# Linux_board_va_1_dxp.net
KiCad netlist of a schematic drawn in Altium Designer
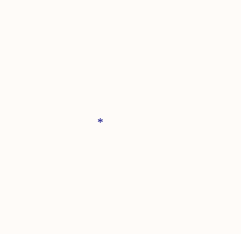
[diagram p0: Linux_board.va_1.dxp.SchDoc, top left]
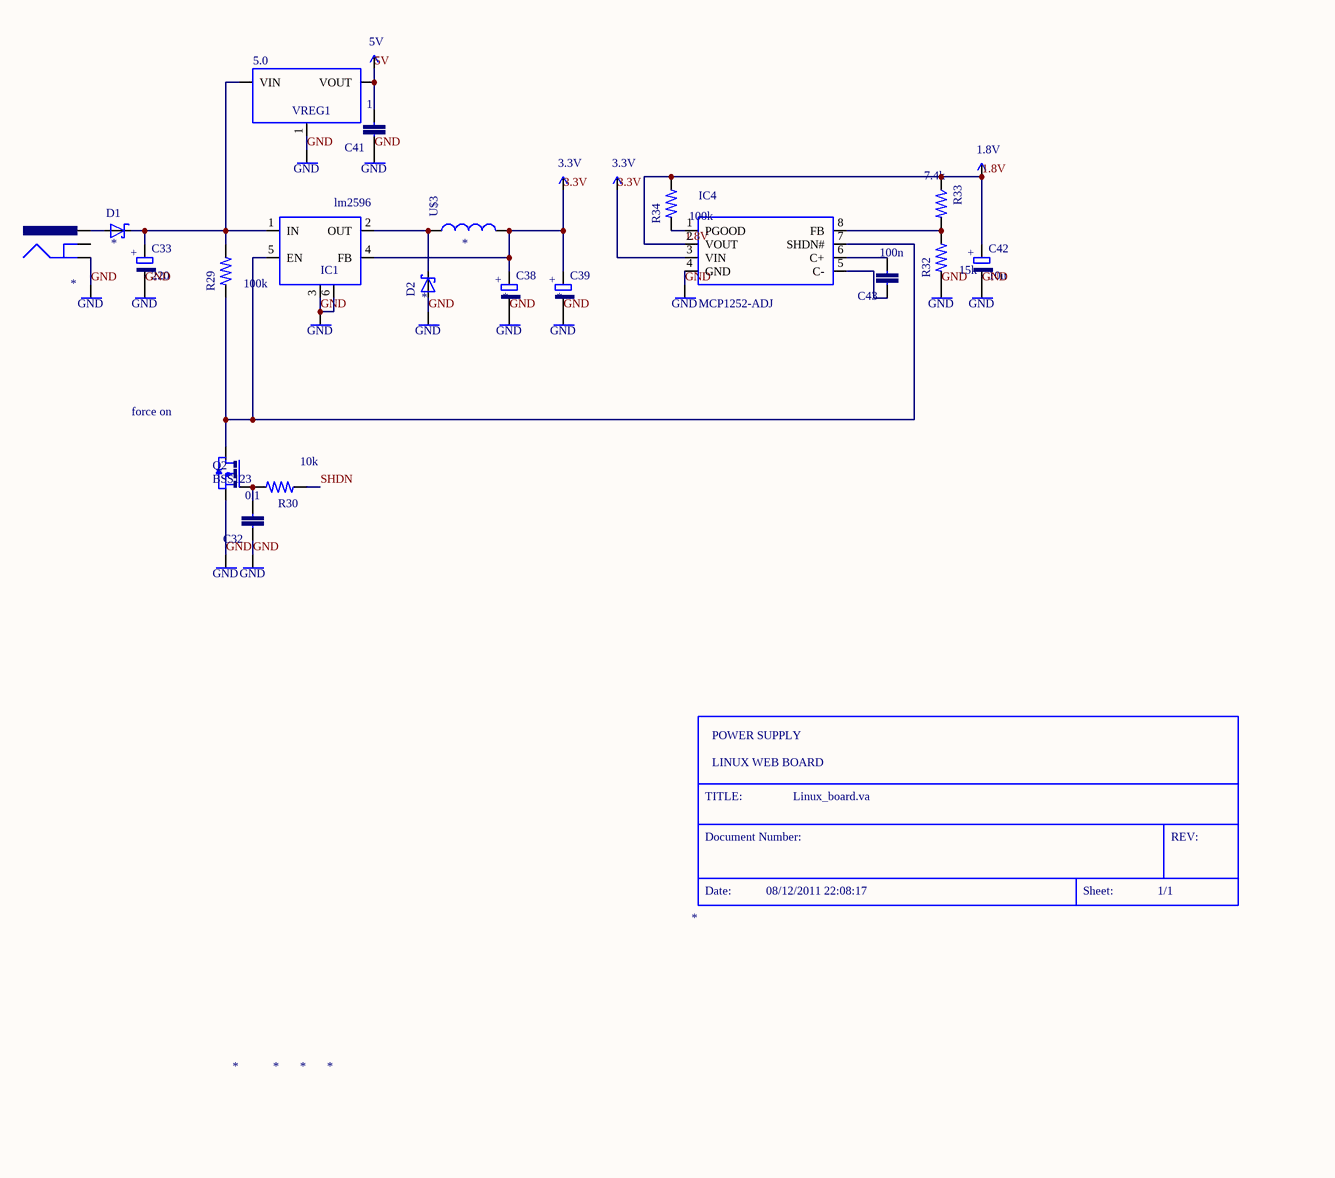
[diagram p1: Linux_board.va_1.dxp.SchDoc, top middle]
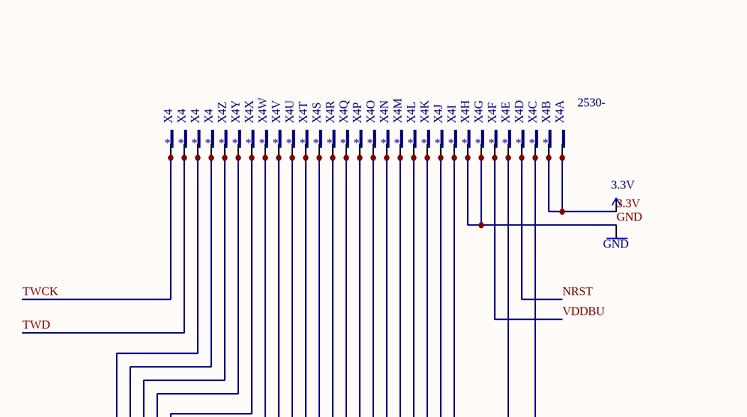
[diagram p2: Linux_board.va_1.dxp.SchDoc, top right]
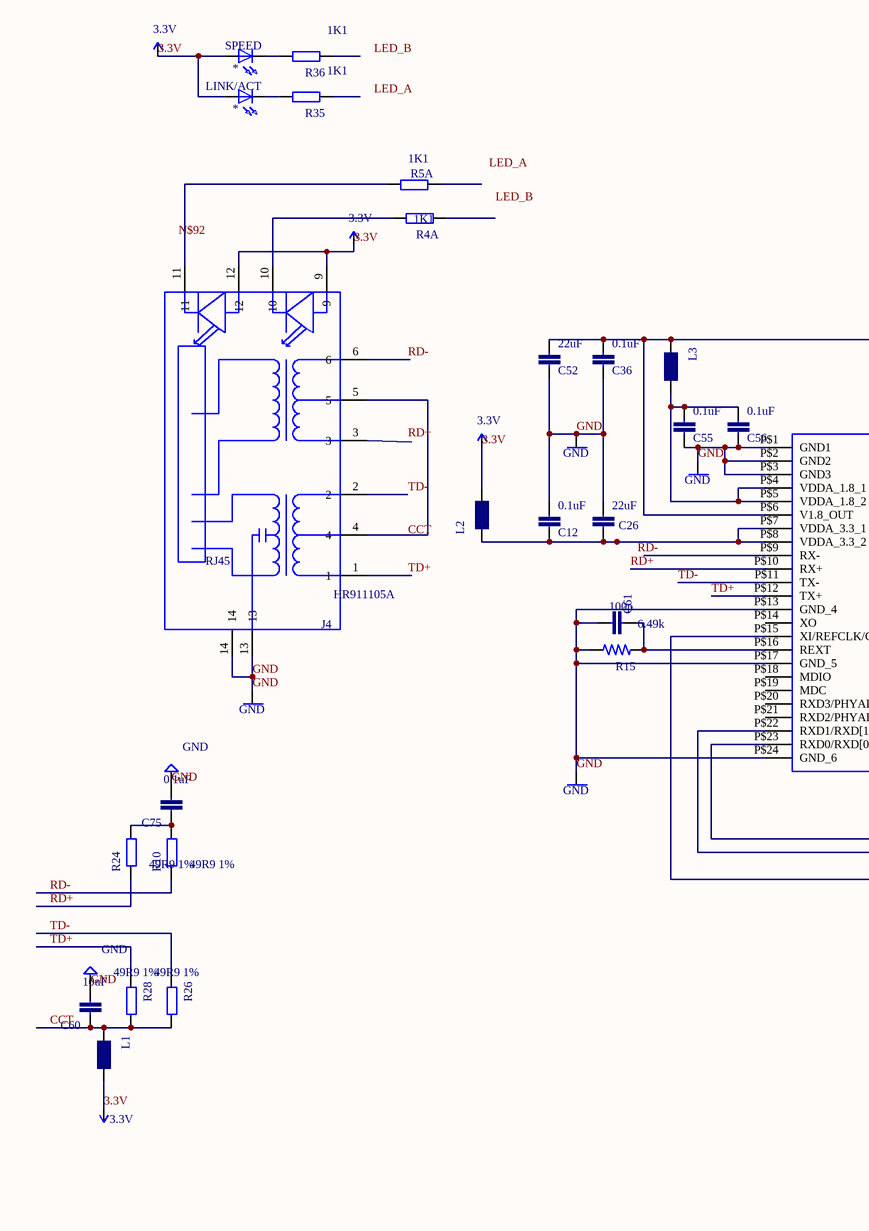
[diagram p3: Linux_board.va_1.dxp.SchDoc, bottom left]
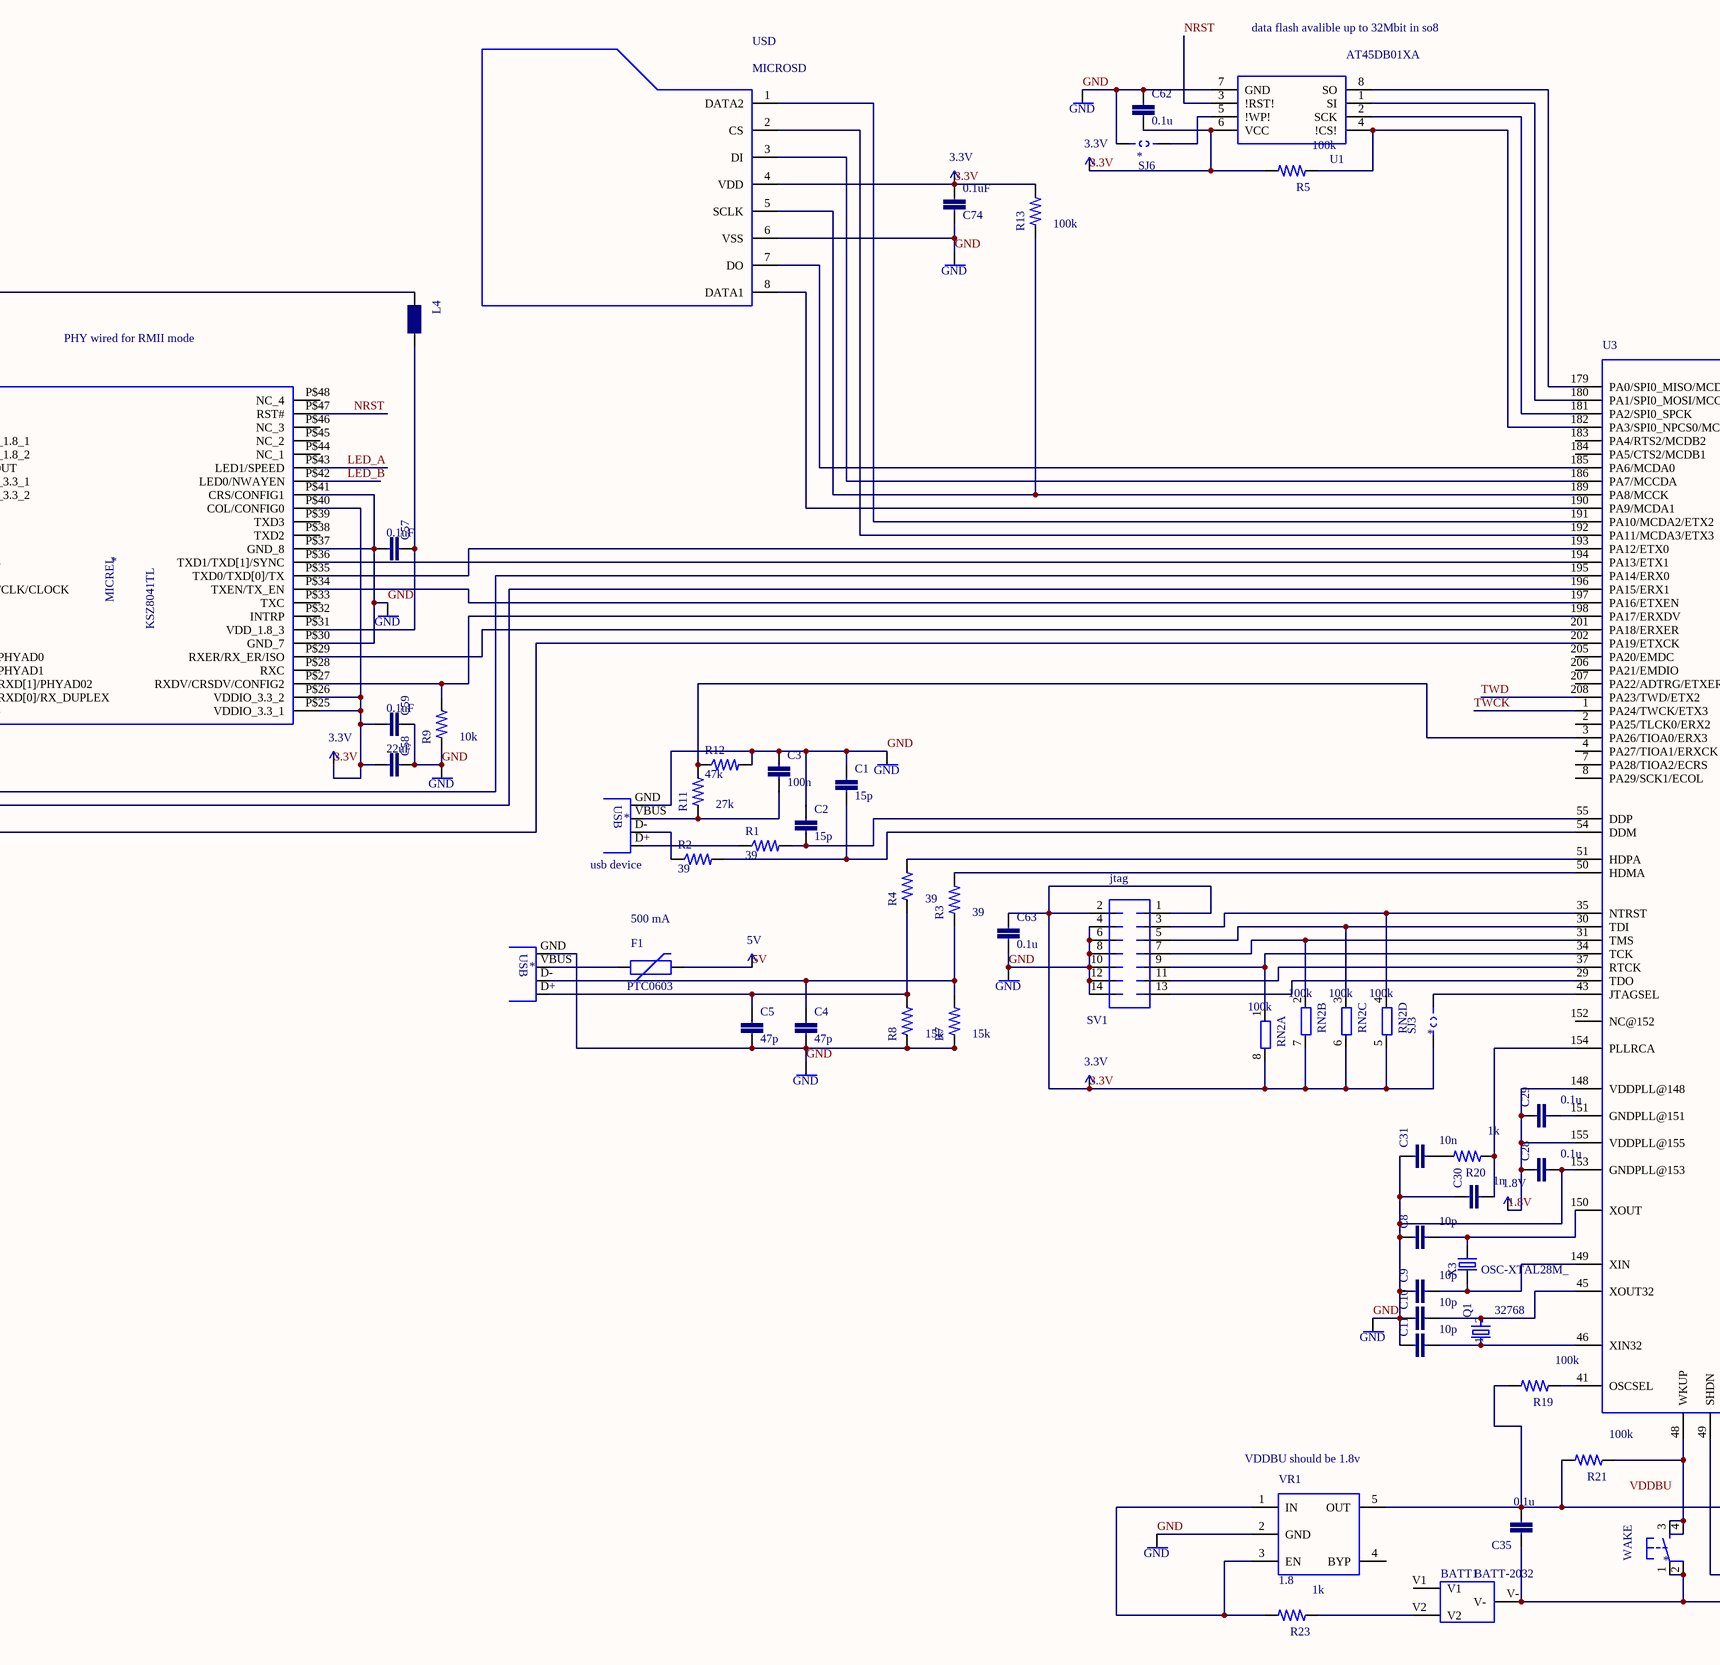
[diagram p4: Linux_board.va_1.dxp.SchDoc, bottom middle]
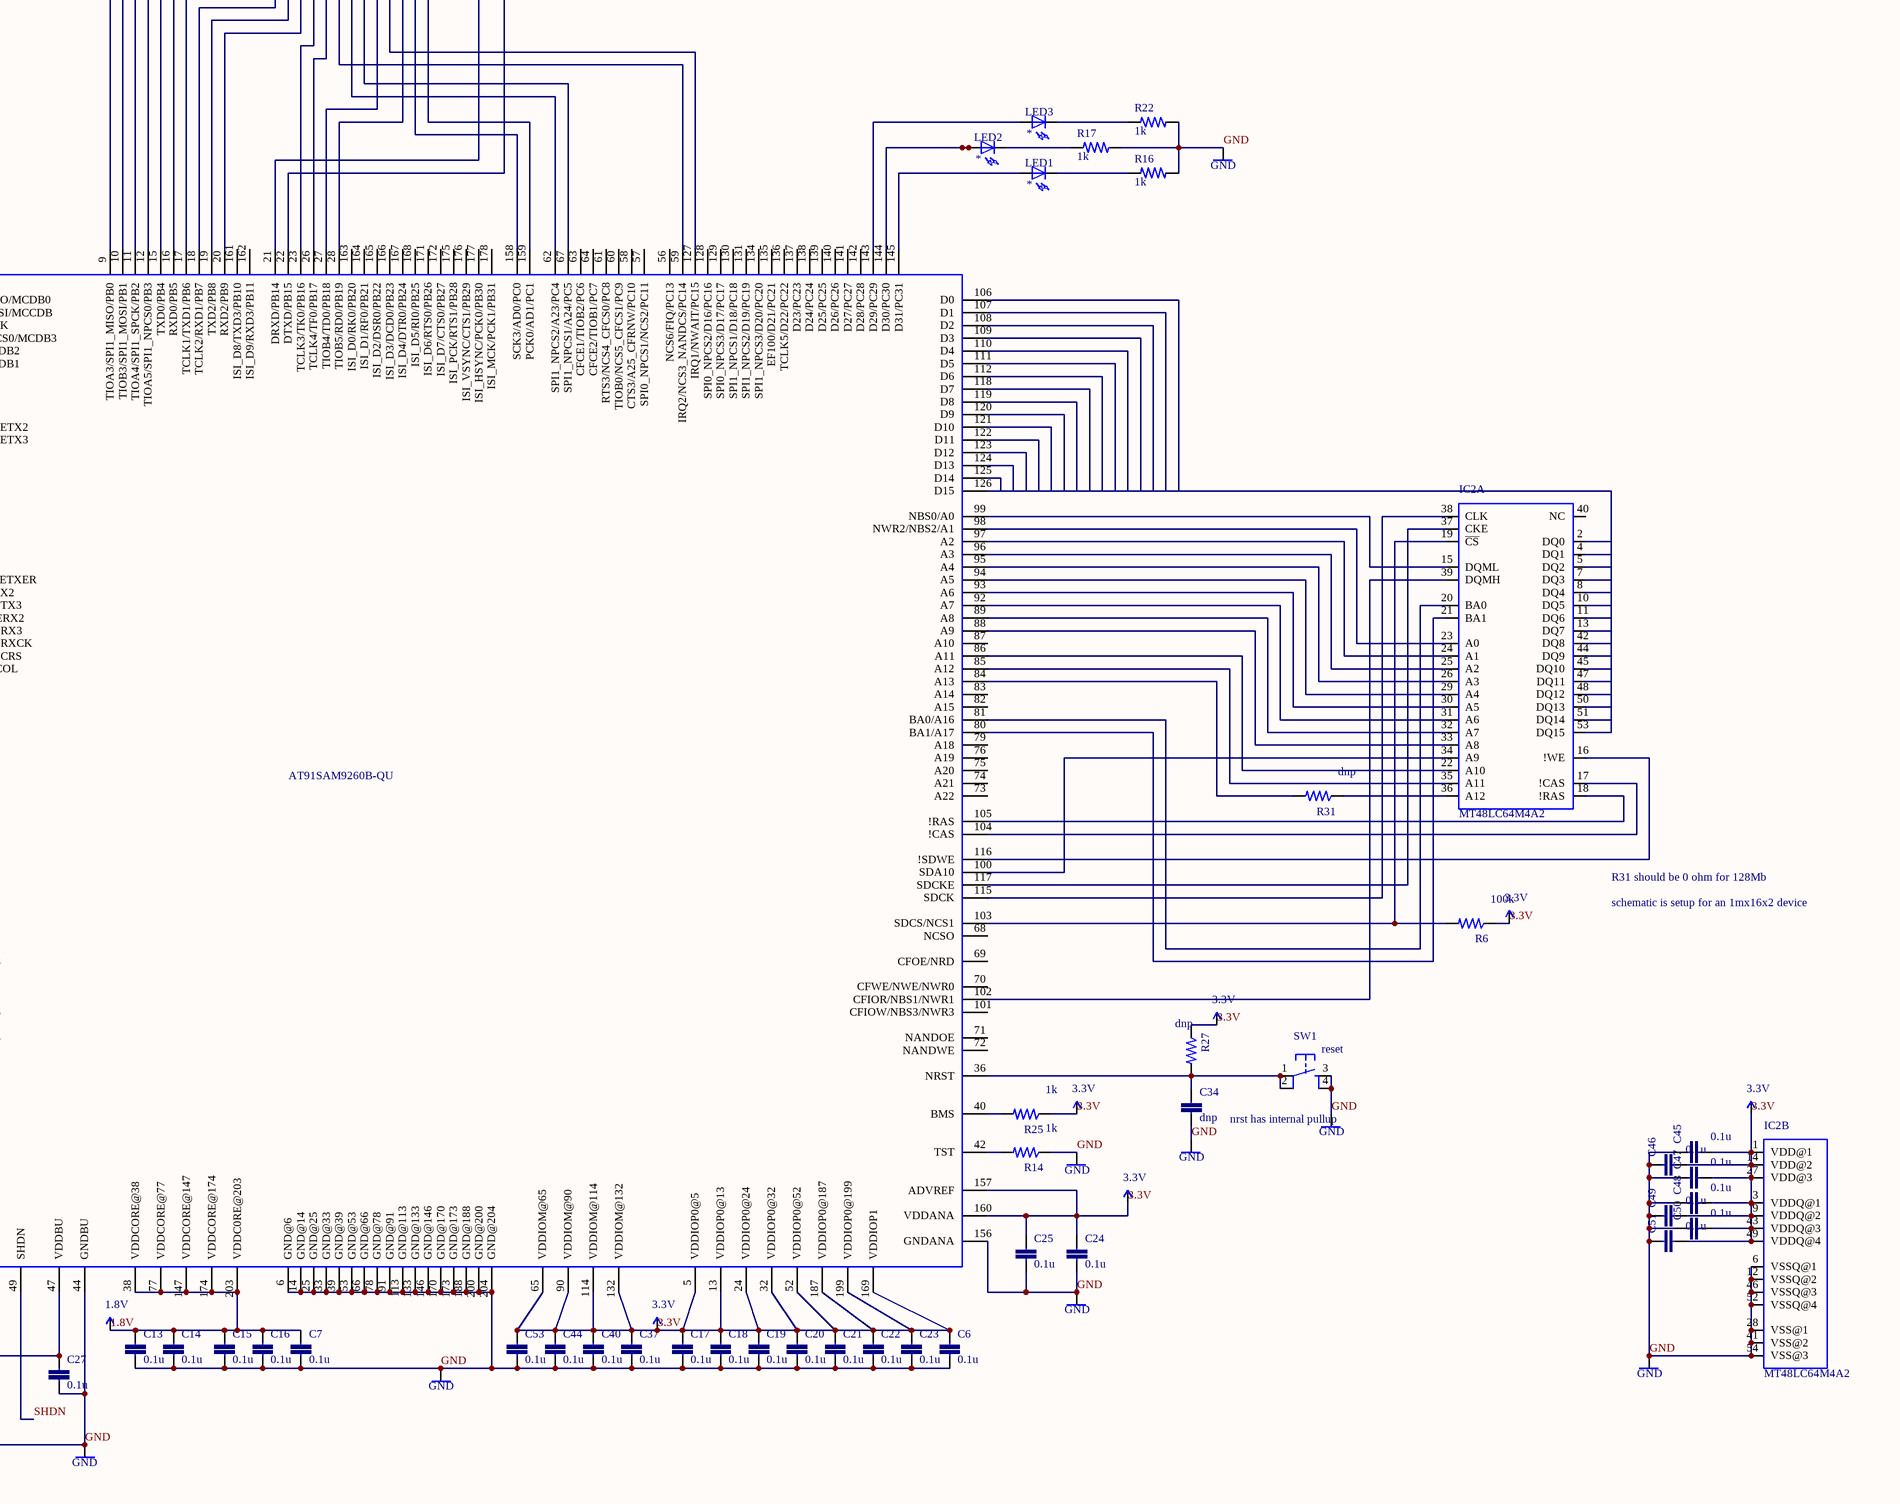
[diagram p5: Linux_board.va_1.dxp.SchDoc, bottom right]

(export (version "E")
  (design (tool "Eeschema 10.0.6"))
  (components
    (comp (ref "BATT1")
      (value "BATT-2032")
      (footprint "2032")
      (libsource (lib "dp_devices") (part "BATT-2032"))
    )
    (comp (ref "C1") (value "15p") (footprint "0603-CAP") (libsource (lib "SparkFun") (part "CAP0603-CAP")))
    (comp (ref "C2") (value "15p") (footprint "0603-CAP") (libsource (lib "SparkFun") (part "CAP0603-CAP")))
    (comp (ref "C3") (value "100n") (footprint "0603-CAP") (libsource (lib "SparkFun") (part "CAP0603-CAP")))
    (comp (ref "C4") (value "47p") (footprint "0603-CAP") (libsource (lib "SparkFun") (part "CAP0603-CAP")))
    (comp (ref "C5") (value "47p") (footprint "0603-CAP") (libsource (lib "SparkFun") (part "CAP0603-CAP")))
    (comp (ref "C6") (value "0.1u") (footprint "0603-CAP") (libsource (lib "SparkFun") (part "CAP0603-CAP")))
    (comp (ref "C7") (value "0.1u") (footprint "0603-CAP") (libsource (lib "SparkFun") (part "CAP0603-CAP")))
    (comp (ref "C8") (value "10p") (footprint "0603-CAP") (libsource (lib "") (part "CAP0603-CAP_1")))
    (comp (ref "C9") (value "10p") (footprint "0603-CAP") (libsource (lib "") (part "CAP0603-CAP_1")))
    (comp (ref "C10") (value "10p") (footprint "0603-CAP") (libsource (lib "") (part "CAP0603-CAP_1")))
    (comp (ref "C11") (value "10p") (footprint "0603-CAP") (libsource (lib "") (part "CAP0603-CAP_1")))
    (comp (ref "C12") (value "0.1uF") (footprint "C0603") (libsource (lib "") (part "C-EUC0603_1")))
    (comp (ref "C13") (value "0.1u") (footprint "0603-CAP") (libsource (lib "SparkFun") (part "CAP0603-CAP")))
    (comp (ref "C14") (value "0.1u") (footprint "0603-CAP") (libsource (lib "SparkFun") (part "CAP0603-CAP")))
    (comp (ref "C15") (value "0.1u") (footprint "0603-CAP") (libsource (lib "SparkFun") (part "CAP0603-CAP")))
    (comp (ref "C16") (value "0.1u") (footprint "0603-CAP") (libsource (lib "SparkFun") (part "CAP0603-CAP")))
    (comp (ref "C17") (value "0.1u") (footprint "0603-CAP") (libsource (lib "SparkFun") (part "CAP0603-CAP")))
    (comp (ref "C18") (value "0.1u") (footprint "0603-CAP") (libsource (lib "SparkFun") (part "CAP0603-CAP")))
    (comp (ref "C19") (value "0.1u") (footprint "0603-CAP") (libsource (lib "SparkFun") (part "CAP0603-CAP")))
    (comp (ref "C20") (value "0.1u") (footprint "0603-CAP") (libsource (lib "SparkFun") (part "CAP0603-CAP")))
    (comp (ref "C21") (value "0.1u") (footprint "0603-CAP") (libsource (lib "SparkFun") (part "CAP0603-CAP")))
    (comp (ref "C22") (value "0.1u") (footprint "0603-CAP") (libsource (lib "SparkFun") (part "CAP0603-CAP")))
    (comp (ref "C23") (value "0.1u") (footprint "0603-CAP") (libsource (lib "SparkFun") (part "CAP0603-CAP")))
    (comp (ref "C24") (value "0.1u") (footprint "0603-CAP") (libsource (lib "SparkFun") (part "CAP0603-CAP")))
    (comp (ref "C25") (value "0.1u") (footprint "0603-CAP") (libsource (lib "SparkFun") (part "CAP0603-CAP")))
    (comp (ref "C26") (value "22uF") (footprint "C0603") (libsource (lib "") (part "C-EUC0603_1")))
    (comp (ref "C27") (value "0.1u") (footprint "0603-CAP") (libsource (lib "SparkFun") (part "CAP0603-CAP")))
    (comp (ref "C28") (value "0.1u") (footprint "0603-CAP") (libsource (lib "") (part "CAP0603-CAP_1")))
    (comp (ref "C29") (value "0.1u") (footprint "0603-CAP") (libsource (lib "") (part "CAP0603-CAP_1")))
    (comp (ref "C30") (value "1n") (footprint "0603-CAP") (libsource (lib "") (part "CAP0603-CAP_1")))
    (comp (ref "C31") (value "10n") (footprint "0603-CAP") (libsource (lib "") (part "CAP0603-CAP_1")))
    (comp (ref "C32") (value "0.1") (footprint "C603") (libsource (lib "dp_devices") (part "CAPC603")))
    (comp (ref "C33") (value "220") (footprint "SMC_B") (libsource (lib "dp_devices") (part "CAP_POLSMC_B")))
    (comp (ref "C34") (value "dnp") (footprint "0603-CAP") (libsource (lib "SparkFun") (part "CAP0603-CAP")))
    (comp (ref "C35") (value "0.1u") (footprint "0603-CAP") (libsource (lib "") (part "CAP0603-CAP_2")))
    (comp (ref "C36") (value "0.1uF") (footprint "C0603") (libsource (lib "") (part "C-EUC0603_1")))
    (comp (ref "C37") (value "0.1u") (footprint "0603-CAP") (libsource (lib "SparkFun") (part "CAP0603-CAP")))
    (comp (ref "C38") (value "*") (footprint "CASE_A") (libsource (lib "dp_devices") (part "CAP_POLCASE_A")))
    (comp (ref "C39") (value "*") (footprint "SMC_B") (libsource (lib "dp_devices") (part "CAP_POLSMC_B")))
    (comp (ref "C40") (value "0.1u") (footprint "0603-CAP") (libsource (lib "SparkFun") (part "CAP0603-CAP")))
    (comp (ref "C41") (value "1") (footprint "C603") (libsource (lib "dp_devices") (part "CAPC603")))
    (comp (ref "C42") (value "10u") (footprint "SMC_B") (libsource (lib "dp_devices") (part "CAP_POLSMC_B")))
    (comp (ref "C43") (value "100n") (footprint "C603") (libsource (lib "dp_devices") (part "CAPC603")))
    (comp (ref "C44") (value "0.1u") (footprint "0603-CAP") (libsource (lib "SparkFun") (part "CAP0603-CAP")))
    (comp (ref "C45") (value "0.1u") (footprint "0603-CAP") (libsource (lib "") (part "CAP0603-CAP_1")))
    (comp (ref "C46") (value "0.1u") (footprint "0603-CAP") (libsource (lib "") (part "CAP0603-CAP_1")))
    (comp (ref "C47") (value "0.1u") (footprint "0603-CAP") (libsource (lib "") (part "CAP0603-CAP_1")))
    (comp (ref "C48") (value "0.1u") (footprint "0603-CAP") (libsource (lib "") (part "CAP0603-CAP_1")))
    (comp (ref "C49") (value "0.1u") (footprint "0603-CAP") (libsource (lib "") (part "CAP0603-CAP_1")))
    (comp (ref "C50") (value "0.1u") (footprint "0603-CAP") (libsource (lib "") (part "CAP0603-CAP_1")))
    (comp (ref "C51") (value "0.1u") (footprint "0603-CAP") (libsource (lib "") (part "CAP0603-CAP_1")))
    (comp (ref "C52") (value "22uF") (footprint "C0603") (libsource (lib "") (part "C-EUC0603_1")))
    (comp (ref "C53") (value "0.1u") (footprint "0603-CAP") (libsource (lib "SparkFun") (part "CAP0603-CAP")))
    (comp (ref "C55") (value "0.1uF") (footprint "C0603") (libsource (lib "") (part "C-EUC0603_1")))
    (comp (ref "C56") (value "0.1uF") (footprint "C0603") (libsource (lib "") (part "C-EUC0603_1")))
    (comp (ref "C57") (value "0.1uF") (footprint "C0603") (libsource (lib "rcl") (part "C-EUC0603")))
    (comp (ref "C58") (value "22uF") (footprint "C0603") (libsource (lib "rcl") (part "C-EUC0603")))
    (comp (ref "C59") (value "0.1uF") (footprint "C0603") (libsource (lib "rcl") (part "C-EUC0603")))
    (comp (ref "C60") (value "10uF") (footprint "C0603") (libsource (lib "") (part "C-EUC0603_2")))
    (comp (ref "C61") (value "100p") (footprint "C0603") (libsource (lib "rcl") (part "C-EUC0603")))
    (comp (ref "C62") (value "0.1u") (footprint "0603-CAP") (libsource (lib "SparkFun") (part "CAP0603-CAP")))
    (comp (ref "C63") (value "0.1u") (footprint "0603-CAP") (libsource (lib "SparkFun") (part "CAP0603-CAP")))
    (comp (ref "C74") (value "0.1uF") (footprint "C0603") (libsource (lib "") (part "C-EUC0603_1")))
    (comp (ref "C75") (value "0.1uF") (footprint "C0603") (libsource (lib "") (part "C-EUC0603_2")))
    (comp (ref "D1") (value "*") (footprint "SMB") (libsource (lib "diode") (part "SCHOTTKY-DIODESMD")))
    (comp (ref "D2") (value "*") (footprint "SMB") (libsource (lib "") (part "SCHOTTKY-DIODESMD_1")))
    (comp (ref "F1") (value "PTC0603") (footprint "0603") (libsource (lib "SparkFun") (part "PTC0603")))
    (comp (ref "FRAME1") (value "*") (libsource (lib "") (part "FRAME_A_L_1")))
    (comp (ref "GND1") (value "GND") (libsource (lib "") (part "GND_1")))
    (comp (ref "GND2") (value "GND") (libsource (lib "") (part "GND_1")))
    (comp (ref "GND3") (value "GND") (libsource (lib "") (part "GND_1")))
    (comp (ref "GND4") (value "GND") (libsource (lib "") (part "GND_1")))
    (comp (ref "GND6") (value "GND") (libsource (lib "") (part "GND_1")))
    (comp (ref "GND7") (value "GND") (libsource (lib "") (part "GND_1")))
    (comp (ref "GND8") (value "GND") (libsource (lib "") (part "GND_1")))
    (comp (ref "GND9") (value "GND") (libsource (lib "") (part "GND_1")))
    (comp (ref "GND10") (value "GND") (libsource (lib "supply1") (part "GND")))
    (comp (ref "GND11") (value "GND") (libsource (lib "supply1") (part "GND")))
    (comp (ref "GND12") (value "GND") (libsource (lib "") (part "GND_1")))
    (comp (ref "GND13") (value "GND") (libsource (lib "supply1") (part "GND")))
    (comp (ref "GND14") (value "GND") (libsource (lib "") (part "GND_1")))
    (comp (ref "GND15") (value "GND") (libsource (lib "supply1") (part "GND")))
    (comp (ref "GND16") (value "GND") (libsource (lib "") (part "GND_1")))
    (comp (ref "GND17") (value "GND") (libsource (lib "") (part "GND_1")))
    (comp (ref "GND18") (value "GND") (libsource (lib "") (part "GND_1")))
    (comp (ref "GND19") (value "GND") (libsource (lib "") (part "GND_1")))
    (comp (ref "GND20") (value "GND") (libsource (lib "") (part "GND_1")))
    (comp (ref "GND21") (value "GND") (libsource (lib "") (part "GND_1")))
    (comp (ref "GND22") (value "GND") (libsource (lib "") (part "GND_1")))
    (comp (ref "GND23") (value "GND") (libsource (lib "supply1") (part "GND")))
    (comp (ref "GND24") (value "GND") (libsource (lib "supply1") (part "GND")))
    (comp (ref "GND25") (value "GND") (libsource (lib "") (part "GND_1")))
    (comp (ref "GND26") (value "GND") (libsource (lib "") (part "GND_1")))
    (comp (ref "GND27") (value "GND") (libsource (lib "") (part "GND_1")))
    (comp (ref "GND28") (value "GND") (libsource (lib "") (part "GND_1")))
    (comp (ref "GND29") (value "GND") (libsource (lib "") (part "GND_1")))
    (comp (ref "GND30") (value "GND") (libsource (lib "") (part "GND_1")))
    (comp (ref "GND31") (value "GND") (libsource (lib "") (part "GND_1")))
    (comp (ref "GND32") (value "GND") (libsource (lib "") (part "GND_1")))
    (comp (ref "GND33") (value "GND") (libsource (lib "") (part "GND_1")))
    (comp (ref "GND34") (value "GND") (libsource (lib "") (part "GND_1")))
    (comp (ref "GND35") (value "GND") (libsource (lib "") (part "GND_1")))
    (comp (ref "GND36") (value "GND") (libsource (lib "") (part "GND_1")))
    (comp (ref "IC1") (value "lm2596") (footprint "TO263-5") (libsource (lib "linear") (part "LM2596S")))
    (comp (ref "IC2")
      (value "MT48LC64M4A2")
      (footprint "TSOP54-400")
      (libsource (lib "") (part "MT48LC64M4A2_1"))
    )
    (comp (ref "IC4")
      (value "MCP1252-ADJ")
      (footprint "MSOP8")
      (libsource (lib "microchip-dspic") (part "MCP1252-ADJ"))
    )
    (comp (ref "J4")
      (value "HR911105A")
      (footprint "HR911105A")
      (fields (field (name "COMMENT_1") "RJ45"))
      (libsource (lib "CONNECTER") (part "HR911105A"))
    )
    (comp (ref "JP1") (value "*") (footprint "STAND-OFF") (libsource (lib "SparkFun") (part "STAND-OFF")))
    (comp (ref "JP2") (value "*") (footprint "STAND-OFF") (libsource (lib "SparkFun") (part "STAND-OFF")))
    (comp (ref "JP3") (value "*") (footprint "STAND-OFF") (libsource (lib "SparkFun") (part "STAND-OFF")))
    (comp (ref "JP4") (value "*") (footprint "STAND-OFF") (libsource (lib "SparkFun") (part "STAND-OFF")))
    (comp (ref "L1")
      (value "*")
      (footprint "WE-KI_0805_B")
      (libsource (lib "wuerth-elektronik") (part "WE-KIL_0805"))
    )
    (comp (ref "L2") (value "*") (footprint "WE-KI_0805_B") (libsource (lib "") (part "WE-KIL_0805_1")))
    (comp (ref "L3")
      (value "*")
      (footprint "WE-KI_0805_B")
      (libsource (lib "wuerth-elektronik") (part "WE-KIL_0805"))
    )
    (comp (ref "L4")
      (value "*")
      (footprint "WE-KI_0805_B")
      (libsource (lib "wuerth-elektronik") (part "WE-KIL_0805"))
    )
    (comp (ref "LED1") (value "*") (footprint "CHIPLED_0805") (libsource (lib "") (part "LEDCHIPLED_0805_1")))
    (comp (ref "LED2") (value "*") (footprint "CHIPLED_0805") (libsource (lib "") (part "LEDCHIPLED_0805_1")))
    (comp (ref "LED3") (value "*") (footprint "CHIPLED_0805") (libsource (lib "") (part "LEDCHIPLED_0805_1")))
    (comp (ref "LINK/ACT")
      (value "*")
      (footprint "CHIPLED_0805")
      (libsource (lib "led") (part "LEDCHIPLED_0805"))
    )
    (comp (ref "P+1") (value "3.3V") (libsource (lib "SparkFun") (part "3.3V")))
    (comp (ref "P+2") (value "3.3V") (libsource (lib "SparkFun") (part "3.3V")))
    (comp (ref "P+3") (value "3.3V") (libsource (lib "SparkFun") (part "3.3V")))
    (comp (ref "P+4") (value "3.3V") (libsource (lib "SparkFun") (part "3.3V")))
    (comp (ref "P+5") (value "3.3V") (libsource (lib "SparkFun") (part "3.3V")))
    (comp (ref "P+6") (value "3.3V") (libsource (lib "SparkFun") (part "3.3V")))
    (comp (ref "P+7") (value "3.3V") (libsource (lib "SparkFun") (part "3.3V")))
    (comp (ref "P+8") (value "3.3V") (libsource (lib "SparkFun") (part "3.3V")))
    (comp (ref "P+9") (value "3.3V") (libsource (lib "SparkFun") (part "3.3V")))
    (comp (ref "P+10") (value "3.3V") (libsource (lib "SparkFun") (part "3.3V")))
    (comp (ref "P+11") (value "3.3V") (libsource (lib "SparkFun") (part "3.3V")))
    (comp (ref "P+12") (value "3.3V") (libsource (lib "SparkFun") (part "3.3V")))
    (comp (ref "P+13") (value "3.3V") (libsource (lib "SparkFun") (part "3.3V")))
    (comp (ref "P+14") (value "3.3V") (libsource (lib "SparkFun") (part "3.3V")))
    (comp (ref "P+15") (value "3.3V") (libsource (lib "SparkFun") (part "3.3V")))
    (comp (ref "P+16") (value "3.3V") (libsource (lib "SparkFun") (part "3.3V")))
    (comp (ref "P+17") (value "3.3V") (libsource (lib "SparkFun") (part "3.3V")))
    (comp (ref "Q1") (value "32768") (footprint "TC26H") (libsource (lib "crystal") (part "CRYSTALTC26H")))
    (comp (ref "Q2")
      (value "BSS123")
      (footprint "SOT23")
      (libsource (lib "transistor-small-signal") (part "BSS123"))
    )
    (comp (ref "R1") (value "39") (footprint "R0603") (libsource (lib "") (part "R-US_R0603_1")))
    (comp (ref "R2") (value "39") (footprint "R0603") (libsource (lib "") (part "R-US_R0603_1")))
    (comp (ref "R3") (value "39") (footprint "R0603") (libsource (lib "resistor") (part "R-US_R0603")))
    (comp (ref "R4") (value "39") (footprint "R0603") (libsource (lib "resistor") (part "R-US_R0603")))
    (comp (ref "R4A") (value "1K1") (footprint "R0603") (libsource (lib "rcl") (part "R-EU_R0603")))
    (comp (ref "R5") (value "100k") (footprint "R0603") (libsource (lib "resistor") (part "R-US_R0603")))
    (comp (ref "R5A") (value "1K1") (footprint "R0603") (libsource (lib "rcl") (part "R-EU_R0603")))
    (comp (ref "R6") (value "100k") (footprint "R0603") (libsource (lib "") (part "R-US_R0603_1")))
    (comp (ref "R7") (value "15k") (footprint "R0603") (libsource (lib "resistor") (part "R-US_R0603")))
    (comp (ref "R8") (value "15k") (footprint "R0603") (libsource (lib "resistor") (part "R-US_R0603")))
    (comp (ref "R9") (value "10k") (footprint "R0603") (libsource (lib "resistor") (part "R-US_R0603")))
    (comp (ref "R10") (value "49R9 1%") (footprint "R0603") (libsource (lib "") (part "R-EU_R0603_1")))
    (comp (ref "R11") (value "27k") (footprint "R0603") (libsource (lib "resistor") (part "R-US_R0603")))
    (comp (ref "R12") (value "47k") (footprint "R0603") (libsource (lib "") (part "R-US_R0603_1")))
    (comp (ref "R13") (value "100k") (footprint "R0603") (libsource (lib "resistor") (part "R-US_R0603")))
    (comp (ref "R14") (value "1k") (footprint "R0603") (libsource (lib "") (part "R-US_R0603_1")))
    (comp (ref "R15") (value "6.49k") (footprint "R0603") (libsource (lib "resistor") (part "R-US_R0603")))
    (comp (ref "R16") (value "1k") (footprint "R0603") (libsource (lib "resistor") (part "R-US_R0603")))
    (comp (ref "R17") (value "1k") (footprint "R0603") (libsource (lib "resistor") (part "R-US_R0603")))
    (comp (ref "R19") (value "100k") (footprint "R0603") (libsource (lib "resistor") (part "R-US_R0603")))
    (comp (ref "R20") (value "1k") (footprint "R0603") (libsource (lib "resistor") (part "R-US_R0603")))
    (comp (ref "R21") (value "100k") (footprint "R0603") (libsource (lib "resistor") (part "R-US_R0603")))
    (comp (ref "R22") (value "1k") (footprint "R0603") (libsource (lib "resistor") (part "R-US_R0603")))
    (comp (ref "R23") (value "1k") (footprint "R0603") (libsource (lib "resistor") (part "R-US_R0603")))
    (comp (ref "R24") (value "49R9 1%") (footprint "R0603") (libsource (lib "") (part "R-EU_R0603_1")))
    (comp (ref "R25") (value "1k") (footprint "R0603") (libsource (lib "") (part "R-US_R0603_1")))
    (comp (ref "R26") (value "49R9 1%") (footprint "R0603") (libsource (lib "rcl") (part "R-EU_R0603")))
    (comp (ref "R27") (value "dnp") (footprint "R0603") (libsource (lib "") (part "R-US_R0603_1")))
    (comp (ref "R28") (value "49R9 1%") (footprint "R0603") (libsource (lib "rcl") (part "R-EU_R0603")))
    (comp (ref "R29") (value "100k") (footprint "R0603") (libsource (lib "resistor") (part "R-US_R0603")))
    (comp (ref "R30") (value "10k") (footprint "R0603") (libsource (lib "resistor") (part "R-US_R0603")))
    (comp (ref "R31") (value "dnp") (footprint "R0603") (libsource (lib "") (part "R-US_R0603_1")))
    (comp (ref "R32") (value "15k") (footprint "R0603") (libsource (lib "resistor") (part "R-US_R0603")))
    (comp (ref "R33") (value "7.4k") (footprint "R0603") (libsource (lib "") (part "R-US_R0603_1")))
    (comp (ref "R34") (value "100k") (footprint "R0603") (libsource (lib "resistor") (part "R-US_R0603")))
    (comp (ref "R35") (value "1K1") (footprint "R0603") (libsource (lib "rcl") (part "R-EU_R0603")))
    (comp (ref "R36") (value "1K1") (footprint "R0603") (libsource (lib "rcl") (part "R-EU_R0603")))
    (comp (ref "RN2") (value "100k") (footprint "RN8P-4R-CRA06S") (libsource (lib "") (part "RNETWORK_2")))
    (comp (ref "SJ3") (value "*") (footprint "SJ_2S-NO") (libsource (lib "SparkFun") (part "SOLDERJUMPERNO")))
    (comp (ref "SJ6") (value "*") (footprint "SJ_2S-NO") (libsource (lib "SparkFun") (part "SOLDERJUMPERNO")))
    (comp (ref "SPEED")
      (value "*")
      (footprint "CHIPLED_0805")
      (libsource (lib "led") (part "LEDCHIPLED_0805"))
    )
    (comp (ref "SV1") (value "jtag") (footprint "MA07-2") (libsource (lib "con-lstb") (part "MA07-2")))
    (comp (ref "SW1")
      (value "reset")
      (footprint "TACT_SWITCH_SMALL")
      (libsource (lib "dp_devices") (part "SW-SMD-SMALL"))
    )
    (comp (ref "U$1") (value "*") (footprint "48PIN-TQFN") (libsource (lib "micrelphy") (part "KSZ8041TL")))
    (comp (ref "U$2")
      (value "*")
      (footprint "POWER_JACK_SMD")
      (libsource (lib "SparkFun-3-2-07") (part "POWER_JACKSMD"))
    )
    (comp (ref "U$3") (value "*") (footprint "CDRH125") (libsource (lib "SparkFun") (part "INDUCTORPWR")))
    (comp (ref "U$4") (value "1.8V") (libsource (lib "SparkFun") (part "1.8V")))
    (comp (ref "U$5") (value "1.8V") (libsource (lib "SparkFun") (part "1.8V")))
    (comp (ref "U$6") (value "1.8V") (libsource (lib "SparkFun") (part "1.8V")))
    (comp (ref "U$7") (value "5V") (libsource (lib "SparkFun") (part "5V")))
    (comp (ref "U$10") (value "5V") (libsource (lib "SparkFun") (part "5V")))
    (comp (ref "U1")
      (value "AT45DB01XA")
      (footprint "SO08W")
      (libsource (lib "memory-atmel") (part "AT45DB01XA"))
    )
    (comp (ref "U3")
      (value "AT91SAM9260B-QU")
      (footprint "PQFP208")
      (libsource (lib "atmel-arm") (part "AT91SAM9260B-QU"))
    )
    (comp (ref "USD") (value "MICROSD") (footprint "MICROSD") (libsource (lib "Seeed") (part "MICROSD")))
    (comp (ref "V7") (value "GND") (libsource (lib "supply2") (part "GND")))
    (comp (ref "V8") (value "GND") (libsource (lib "supply2") (part "GND")))
    (comp (ref "VR1") (value "1.8") (footprint "SOT-23-5") (libsource (lib "dp_devices") (part "MIC5205")))
    (comp (ref "VREG1")
      (value "5.0")
      (footprint "SOT223")
      (libsource (lib "dp_devices") (part "LD1117-3.3SOT223"))
    )
    (comp (ref "WAKE")
      (value "*")
      (footprint "TACT_SWITCH_SMALL")
      (libsource (lib "dp_devices") (part "SW-SMD-SMALL"))
    )
    (comp (ref "X1") (value "*") (footprint "USB-MB-S") (libsource (lib "con-usb") (part "USB-MB-S")))
    (comp (ref "X2") (value "*") (footprint "USB-A-H") (libsource (lib "con-usb") (part "USB-A-H")))
    (comp (ref "X3")
      (value "OSC-XTAL28M_")
      (footprint "5X8")
      (libsource (lib "dp_devices") (part "OSC-XTAL28M_"))
    )
    (comp (ref "X4") (value "2530-") (footprint "PAK100/2500-30") (libsource (lib "") (part "2530-_3")))
  )
  (nets
    (net (code "1") (name "/1.8V") (class "Default")
      (node (ref "C13") (pin "1") (pinfunction "1_1") (pintype "passive"))
      (node (ref "C14") (pin "1") (pinfunction "1_1") (pintype "passive"))
      (node (ref "C15") (pin "1") (pinfunction "1_1") (pintype "passive"))
      (node (ref "C16") (pin "1") (pinfunction "1_1") (pintype "passive"))
      (node (ref "C28") (pin "1") (pinfunction "1_1") (pintype "passive"))
      (node (ref "C29") (pin "1") (pinfunction "1_1") (pintype "passive"))
      (node (ref "C42") (pin "+") (pinfunction "+_+") (pintype "passive"))
      (node (ref "C7") (pin "1") (pinfunction "1_1") (pintype "passive"))
      (node (ref "IC4") (pin "2") (pinfunction "VOUT_2") (pintype "passive"))
      (node (ref "R33") (pin "1") (pinfunction "1_1") (pintype "passive"))
      (node (ref "R34") (pin "2") (pinfunction "2_2") (pintype "passive"))
      (node (ref "U$4") (pin "0") (pinfunction "1.8V_0") (pintype "passive"))
      (node (ref "U$5") (pin "0") (pinfunction "1.8V_0") (pintype "passive"))
      (node (ref "U$6") (pin "0") (pinfunction "1.8V_0") (pintype "passive"))
      (node (ref "U3") (pin "147") (pinfunction "VDDCORE@147_147") (pintype "passive"))
      (node (ref "U3") (pin "148") (pinfunction "VDDPLL@148_148") (pintype "passive"))
      (node (ref "U3") (pin "155") (pinfunction "VDDPLL@155_155") (pintype "passive"))
      (node (ref "U3") (pin "174") (pinfunction "VDDCORE@174_174") (pintype "passive"))
      (node (ref "U3") (pin "203") (pinfunction "VDDC0RE@203_203") (pintype "passive"))
      (node (ref "U3") (pin "38") (pinfunction "VDDCORE@38_38") (pintype "passive"))
      (node (ref "U3") (pin "77") (pinfunction "VDDCORE@77_77") (pintype "passive"))
    )
    (net (code "2") (name "/3.3V") (class "Default")
      (node (ref "C17") (pin "1") (pinfunction "1_1") (pintype "passive"))
      (node (ref "C18") (pin "1") (pinfunction "1_1") (pintype "passive"))
      (node (ref "C19") (pin "1") (pinfunction "1_1") (pintype "passive"))
      (node (ref "C20") (pin "1") (pinfunction "1_1") (pintype "passive"))
      (node (ref "C21") (pin "1") (pinfunction "1_1") (pintype "passive"))
      (node (ref "C22") (pin "1") (pinfunction "1_1") (pintype "passive"))
      (node (ref "C23") (pin "1") (pinfunction "1_1") (pintype "passive"))
      (node (ref "C24") (pin "1") (pinfunction "1_1") (pintype "passive"))
      (node (ref "C25") (pin "1") (pinfunction "1_1") (pintype "passive"))
      (node (ref "C37") (pin "1") (pinfunction "1_1") (pintype "passive"))
      (node (ref "C38") (pin "+") (pinfunction "+_+") (pintype "passive"))
      (node (ref "C39") (pin "+") (pinfunction "+_+") (pintype "passive"))
      (node (ref "C40") (pin "1") (pinfunction "1_1") (pintype "passive"))
      (node (ref "C44") (pin "1") (pinfunction "1_1") (pintype "passive"))
      (node (ref "C45") (pin "2") (pinfunction "2_2") (pintype "passive"))
      (node (ref "C46") (pin "2") (pinfunction "2_2") (pintype "passive"))
      (node (ref "C47") (pin "2") (pinfunction "2_2") (pintype "passive"))
      (node (ref "C48") (pin "2") (pinfunction "2_2") (pintype "passive"))
      (node (ref "C49") (pin "2") (pinfunction "2_2") (pintype "passive"))
      (node (ref "C50") (pin "2") (pinfunction "2_2") (pintype "passive"))
      (node (ref "C51") (pin "2") (pinfunction "2_2") (pintype "passive"))
      (node (ref "C53") (pin "1") (pinfunction "1_1") (pintype "passive"))
      (node (ref "C58") (pin "1") (pinfunction "1_1") (pintype "passive"))
      (node (ref "C59") (pin "1") (pinfunction "1_1") (pintype "passive"))
      (node (ref "C6") (pin "1") (pinfunction "1_1") (pintype "passive"))
      (node (ref "C62") (pin "2") (pinfunction "2_2") (pintype "passive"))
      (node (ref "C63") (pin "1") (pinfunction "1_1") (pintype "passive"))
      (node (ref "C74") (pin "1") (pinfunction "1_1") (pintype "passive"))
      (node (ref "IC1") (pin "4") (pinfunction "FB_4") (pintype "passive"))
      (node (ref "IC2") (pin "1") (pinfunction "VDD@1_1") (pintype "passive"))
      (node (ref "IC2") (pin "14") (pinfunction "VDD@2_14") (pintype "passive"))
      (node (ref "IC2") (pin "27") (pinfunction "VDD@3_27") (pintype "passive"))
      (node (ref "IC2") (pin "3") (pinfunction "VDDQ@1_3") (pintype "passive"))
      (node (ref "IC2") (pin "43") (pinfunction "VDDQ@3_43") (pintype "passive"))
      (node (ref "IC2") (pin "49") (pinfunction "VDDQ@4_49") (pintype "passive"))
      (node (ref "IC2") (pin "9") (pinfunction "VDDQ@2_9") (pintype "passive"))
      (node (ref "IC4") (pin "3") (pinfunction "VIN_3") (pintype "passive"))
      (node (ref "J4") (pin "12") (pinfunction "12_12") (pintype "passive"))
      (node (ref "J4") (pin "9") (pinfunction "9_9") (pintype "passive"))
      (node (ref "L1") (pin "1") (pinfunction "2_1") (pintype "passive"))
      (node (ref "L2") (pin "1") (pinfunction "2_1") (pintype "passive"))
      (node (ref "LINK/ACT") (pin "A") (pinfunction "A_A") (pintype "passive"))
      (node (ref "P+1") (pin "0") (pinfunction "3.3V_0") (pintype "passive"))
      (node (ref "P+10") (pin "0") (pinfunction "3.3V_0") (pintype "passive"))
      (node (ref "P+11") (pin "0") (pinfunction "3.3V_0") (pintype "passive"))
      (node (ref "P+12") (pin "0") (pinfunction "3.3V_0") (pintype "passive"))
      (node (ref "P+13") (pin "0") (pinfunction "3.3V_0") (pintype "passive"))
      (node (ref "P+14") (pin "0") (pinfunction "3.3V_0") (pintype "passive"))
      (node (ref "P+15") (pin "0") (pinfunction "3.3V_0") (pintype "passive"))
      (node (ref "P+16") (pin "0") (pinfunction "3.3V_0") (pintype "passive"))
      (node (ref "P+17") (pin "0") (pinfunction "3.3V_0") (pintype "passive"))
      (node (ref "P+2") (pin "0") (pinfunction "3.3V_0") (pintype "passive"))
      (node (ref "P+3") (pin "0") (pinfunction "3.3V_0") (pintype "passive"))
      (node (ref "P+4") (pin "0") (pinfunction "3.3V_0") (pintype "passive"))
      (node (ref "P+5") (pin "0") (pinfunction "3.3V_0") (pintype "passive"))
      (node (ref "P+6") (pin "0") (pinfunction "3.3V_0") (pintype "passive"))
      (node (ref "P+7") (pin "0") (pinfunction "3.3V_0") (pintype "passive"))
      (node (ref "P+8") (pin "0") (pinfunction "3.3V_0") (pintype "passive"))
      (node (ref "P+9") (pin "0") (pinfunction "3.3V_0") (pintype "passive"))
      (node (ref "R13") (pin "2") (pinfunction "2_2") (pintype "passive"))
      (node (ref "R25") (pin "1") (pinfunction "1_1") (pintype "passive"))
      (node (ref "R27") (pin "1") (pinfunction "1_1") (pintype "passive"))
      (node (ref "R5") (pin "2") (pinfunction "2_2") (pintype "passive"))
      (node (ref "R6") (pin "1") (pinfunction "1_1") (pintype "passive"))
      (node (ref "RN2") (pin "5") (pinfunction "2_5") (pintype "passive"))
      (node (ref "RN2") (pin "6") (pinfunction "2_6") (pintype "passive"))
      (node (ref "RN2") (pin "7") (pinfunction "2_7") (pintype "passive"))
      (node (ref "RN2") (pin "8") (pinfunction "2_8") (pintype "passive"))
      (node (ref "SJ3") (pin "1") (pinfunction "1_1") (pintype "passive"))
      (node (ref "SPEED") (pin "A") (pinfunction "A_A") (pintype "passive"))
      (node (ref "SV1") (pin "1") (pinfunction "1_1") (pintype "passive"))
      (node (ref "SV1") (pin "2") (pinfunction "2_2") (pintype "passive"))
      (node (ref "U$1") (pin "P$25") (pinfunction "VDDIO_3.3_1_P$25") (pintype "passive"))
      (node (ref "U$1") (pin "P$26") (pinfunction "VDDIO_3.3_2_P$26") (pintype "passive"))
      (node (ref "U$1") (pin "P$40") (pinfunction "COL/CONFIG0_P$40") (pintype "passive"))
      (node (ref "U$3") (pin "2") (pinfunction "2_2") (pintype "passive"))
      (node (ref "U1") (pin "6") (pinfunction "VCC_6") (pintype "passive"))
      (node (ref "U3") (pin "114") (pinfunction "VDDIOM@114_114") (pintype "passive"))
      (node (ref "U3") (pin "13") (pinfunction "VDDIOP0@13_13") (pintype "passive"))
      (node (ref "U3") (pin "132") (pinfunction "VDDIOM@132_132") (pintype "passive"))
      (node (ref "U3") (pin "157") (pinfunction "ADVREF_157") (pintype "passive"))
      (node (ref "U3") (pin "160") (pinfunction "VDDANA_160") (pintype "passive"))
      (node (ref "U3") (pin "169") (pinfunction "VDDIOP1_169") (pintype "passive"))
      (node (ref "U3") (pin "187") (pinfunction "VDDIOP0@187_187") (pintype "passive"))
      (node (ref "U3") (pin "199") (pinfunction "VDDIOP0@199_199") (pintype "passive"))
      (node (ref "U3") (pin "24") (pinfunction "VDDIOP0@24_24") (pintype "passive"))
      (node (ref "U3") (pin "32") (pinfunction "VDDIOP0@32_32") (pintype "passive"))
      (node (ref "U3") (pin "5") (pinfunction "VDDIOP0@5_5") (pintype "passive"))
      (node (ref "U3") (pin "52") (pinfunction "VDDIOP0@52_52") (pintype "passive"))
      (node (ref "U3") (pin "65") (pinfunction "VDDIOM@65_65") (pintype "passive"))
      (node (ref "U3") (pin "90") (pinfunction "VDDIOM@90_90") (pintype "passive"))
      (node (ref "USD") (pin "4") (pinfunction "VDD_4") (pintype "passive"))
      (node (ref "X4") (pin "1") (pinfunction "KL_1") (pintype "passive"))
      (node (ref "X4") (pin "2") (pinfunction "KL_2") (pintype "passive"))
    )
    (net (code "3") (name "/5V") (class "Default")
      (node (ref "C41") (pin "2") (pinfunction "2_2") (pintype "passive"))
      (node (ref "F1") (pin "2") (pinfunction "2_2") (pintype "passive"))
      (node (ref "U$10") (pin "0") (pinfunction "5V_0") (pintype "passive"))
      (node (ref "U$7") (pin "0") (pinfunction "5V_0") (pintype "passive"))
      (node (ref "VREG1") (pin "2") (pinfunction "VOUT_2") (pintype "passive"))
    )
    (net (code "4") (name "/CCT") (class "Default")
      (node (ref "C60") (pin "1") (pinfunction "1_1") (pintype "passive"))
      (node (ref "L1") (pin "2") (pinfunction "1_2") (pintype "passive"))
      (node (ref "R26") (pin "2") (pinfunction "2_2") (pintype "passive"))
      (node (ref "R28") (pin "2") (pinfunction "2_2") (pintype "passive"))
    )
    (net (code "5") (name "/GND") (class "Default")
      (node (ref "BATT1") (pin "V-") (pinfunction "V-_V-") (pintype "passive"))
      (node (ref "C1") (pin "1") (pinfunction "1_1") (pintype "passive"))
      (node (ref "C10") (pin "1") (pinfunction "1_1") (pintype "passive"))
      (node (ref "C11") (pin "1") (pinfunction "1_1") (pintype "passive"))
      (node (ref "C12") (pin "1") (pinfunction "1_1") (pintype "passive"))
      (node (ref "C13") (pin "2") (pinfunction "2_2") (pintype "passive"))
      (node (ref "C14") (pin "2") (pinfunction "2_2") (pintype "passive"))
      (node (ref "C15") (pin "2") (pinfunction "2_2") (pintype "passive"))
      (node (ref "C16") (pin "2") (pinfunction "2_2") (pintype "passive"))
      (node (ref "C17") (pin "2") (pinfunction "2_2") (pintype "passive"))
      (node (ref "C18") (pin "2") (pinfunction "2_2") (pintype "passive"))
      (node (ref "C19") (pin "2") (pinfunction "2_2") (pintype "passive"))
      (node (ref "C2") (pin "1") (pinfunction "1_1") (pintype "passive"))
      (node (ref "C20") (pin "2") (pinfunction "2_2") (pintype "passive"))
      (node (ref "C21") (pin "2") (pinfunction "2_2") (pintype "passive"))
      (node (ref "C22") (pin "2") (pinfunction "2_2") (pintype "passive"))
      (node (ref "C23") (pin "2") (pinfunction "2_2") (pintype "passive"))
      (node (ref "C24") (pin "2") (pinfunction "2_2") (pintype "passive"))
      (node (ref "C25") (pin "2") (pinfunction "2_2") (pintype "passive"))
      (node (ref "C26") (pin "1") (pinfunction "1_1") (pintype "passive"))
      (node (ref "C27") (pin "2") (pinfunction "2_2") (pintype "passive"))
      (node (ref "C28") (pin "2") (pinfunction "2_2") (pintype "passive"))
      (node (ref "C3") (pin "1") (pinfunction "1_1") (pintype "passive"))
      (node (ref "C30") (pin "1") (pinfunction "1_1") (pintype "passive"))
      (node (ref "C31") (pin "1") (pinfunction "1_1") (pintype "passive"))
      (node (ref "C32") (pin "1") (pinfunction "1_1") (pintype "passive"))
      (node (ref "C33") (pin "-") (pinfunction "-_-") (pintype "passive"))
      (node (ref "C34") (pin "2") (pinfunction "2_2") (pintype "passive"))
      (node (ref "C35") (pin "1") (pinfunction "1_1") (pintype "passive"))
      (node (ref "C36") (pin "2") (pinfunction "2_2") (pintype "passive"))
      (node (ref "C37") (pin "2") (pinfunction "2_2") (pintype "passive"))
      (node (ref "C38") (pin "-") (pinfunction "-_-") (pintype "passive"))
      (node (ref "C39") (pin "-") (pinfunction "-_-") (pintype "passive"))
      (node (ref "C4") (pin "2") (pinfunction "2_2") (pintype "passive"))
      (node (ref "C40") (pin "2") (pinfunction "2_2") (pintype "passive"))
      (node (ref "C41") (pin "1") (pinfunction "1_1") (pintype "passive"))
      (node (ref "C42") (pin "-") (pinfunction "-_-") (pintype "passive"))
      (node (ref "C44") (pin "2") (pinfunction "2_2") (pintype "passive"))
      (node (ref "C45") (pin "1") (pinfunction "1_1") (pintype "passive"))
      (node (ref "C46") (pin "1") (pinfunction "1_1") (pintype "passive"))
      (node (ref "C47") (pin "1") (pinfunction "1_1") (pintype "passive"))
      (node (ref "C48") (pin "1") (pinfunction "1_1") (pintype "passive"))
      (node (ref "C49") (pin "1") (pinfunction "1_1") (pintype "passive"))
      (node (ref "C5") (pin "2") (pinfunction "2_2") (pintype "passive"))
      (node (ref "C50") (pin "1") (pinfunction "1_1") (pintype "passive"))
      (node (ref "C51") (pin "1") (pinfunction "1_1") (pintype "passive"))
      (node (ref "C52") (pin "2") (pinfunction "2_2") (pintype "passive"))
      (node (ref "C53") (pin "2") (pinfunction "2_2") (pintype "passive"))
      (node (ref "C55") (pin "2") (pinfunction "2_2") (pintype "passive"))
      (node (ref "C56") (pin "2") (pinfunction "2_2") (pintype "passive"))
      (node (ref "C57") (pin "1") (pinfunction "1_1") (pintype "passive"))
      (node (ref "C58") (pin "2") (pinfunction "2_2") (pintype "passive"))
      (node (ref "C59") (pin "2") (pinfunction "2_2") (pintype "passive"))
      (node (ref "C6") (pin "2") (pinfunction "2_2") (pintype "passive"))
      (node (ref "C60") (pin "2") (pinfunction "2_2") (pintype "passive"))
      (node (ref "C61") (pin "1") (pinfunction "1_1") (pintype "passive"))
      (node (ref "C62") (pin "1") (pinfunction "1_1") (pintype "passive"))
      (node (ref "C63") (pin "2") (pinfunction "2_2") (pintype "passive"))
      (node (ref "C7") (pin "2") (pinfunction "2_2") (pintype "passive"))
      (node (ref "C74") (pin "2") (pinfunction "2_2") (pintype "passive"))
      (node (ref "C75") (pin "2") (pinfunction "2_2") (pintype "passive"))
      (node (ref "C8") (pin "1") (pinfunction "1_1") (pintype "passive"))
      (node (ref "C9") (pin "1") (pinfunction "1_1") (pintype "passive"))
      (node (ref "D2") (pin "A") (pinfunction "A_A") (pintype "passive"))
      (node (ref "GND1") (pin "0") (pinfunction "GND_0") (pintype "passive"))
      (node (ref "GND10") (pin "0") (pinfunction "GND_0") (pintype "passive"))
      (node (ref "GND11") (pin "0") (pinfunction "GND_0") (pintype "passive"))
      (node (ref "GND12") (pin "0") (pinfunction "GND_0") (pintype "passive"))
      (node (ref "GND13") (pin "0") (pinfunction "GND_0") (pintype "passive"))
      (node (ref "GND14") (pin "0") (pinfunction "GND_0") (pintype "passive"))
      (node (ref "GND15") (pin "0") (pinfunction "GND_0") (pintype "passive"))
      (node (ref "GND16") (pin "0") (pinfunction "GND_0") (pintype "passive"))
      (node (ref "GND17") (pin "0") (pinfunction "GND_0") (pintype "passive"))
      (node (ref "GND18") (pin "0") (pinfunction "GND_0") (pintype "passive"))
      (node (ref "GND19") (pin "0") (pinfunction "GND_0") (pintype "passive"))
      (node (ref "GND2") (pin "0") (pinfunction "GND_0") (pintype "passive"))
      (node (ref "GND20") (pin "0") (pinfunction "GND_0") (pintype "passive"))
      (node (ref "GND21") (pin "0") (pinfunction "GND_0") (pintype "passive"))
      (node (ref "GND22") (pin "0") (pinfunction "GND_0") (pintype "passive"))
      (node (ref "GND23") (pin "0") (pinfunction "GND_0") (pintype "passive"))
      (node (ref "GND24") (pin "0") (pinfunction "GND_0") (pintype "passive"))
      (node (ref "GND25") (pin "0") (pinfunction "GND_0") (pintype "passive"))
      (node (ref "GND26") (pin "0") (pinfunction "GND_0") (pintype "passive"))
      (node (ref "GND27") (pin "0") (pinfunction "GND_0") (pintype "passive"))
      (node (ref "GND28") (pin "0") (pinfunction "GND_0") (pintype "passive"))
      (node (ref "GND29") (pin "0") (pinfunction "GND_0") (pintype "passive"))
      (node (ref "GND3") (pin "0") (pinfunction "GND_0") (pintype "passive"))
      (node (ref "GND30") (pin "0") (pinfunction "GND_0") (pintype "passive"))
      (node (ref "GND31") (pin "0") (pinfunction "GND_0") (pintype "passive"))
      (node (ref "GND32") (pin "0") (pinfunction "GND_0") (pintype "passive"))
      (node (ref "GND33") (pin "0") (pinfunction "GND_0") (pintype "passive"))
      (node (ref "GND34") (pin "0") (pinfunction "GND_0") (pintype "passive"))
      (node (ref "GND35") (pin "0") (pinfunction "GND_0") (pintype "passive"))
      (node (ref "GND36") (pin "0") (pinfunction "GND_0") (pintype "passive"))
      (node (ref "GND4") (pin "0") (pinfunction "GND_0") (pintype "passive"))
      (node (ref "GND6") (pin "0") (pinfunction "GND_0") (pintype "passive"))
      (node (ref "GND7") (pin "0") (pinfunction "GND_0") (pintype "passive"))
      (node (ref "GND8") (pin "0") (pinfunction "GND_0") (pintype "passive"))
      (node (ref "GND9") (pin "0") (pinfunction "GND_0") (pintype "passive"))
      (node (ref "IC1") (pin "3") (pinfunction "GND_3") (pintype "passive"))
      (node (ref "IC1") (pin "6") (pinfunction "GND@1_6") (pintype "passive"))
      (node (ref "IC2") (pin "12") (pinfunction "VSSQ@2_12") (pintype "passive"))
      (node (ref "IC2") (pin "28") (pinfunction "VSS@1_28") (pintype "passive"))
      (node (ref "IC2") (pin "41") (pinfunction "VSS@2_41") (pintype "passive"))
      (node (ref "IC2") (pin "46") (pinfunction "VSSQ@3_46") (pintype "passive"))
      (node (ref "IC2") (pin "52") (pinfunction "VSSQ@4_52") (pintype "passive"))
      (node (ref "IC2") (pin "54") (pinfunction "VSS@3_54") (pintype "passive"))
      (node (ref "IC2") (pin "6") (pinfunction "VSSQ@1_6") (pintype "passive"))
      (node (ref "IC4") (pin "4") (pinfunction "GND_4") (pintype "passive"))
      (node (ref "J4") (pin "13") (pinfunction "13_13") (pintype "passive"))
      (node (ref "J4") (pin "14") (pinfunction "14_14") (pintype "passive"))
      (node (ref "Q2") (pin "2") (pinfunction "S_2") (pintype "passive"))
      (node (ref "R12") (pin "2") (pinfunction "2_2") (pintype "passive"))
      (node (ref "R14") (pin "1") (pinfunction "1_1") (pintype "passive"))
      (node (ref "R15") (pin "2") (pinfunction "2_2") (pintype "passive"))
      (node (ref "R16") (pin "2") (pinfunction "2_2") (pintype "passive"))
      (node (ref "R17") (pin "2") (pinfunction "2_2") (pintype "passive"))
      (node (ref "R22") (pin "2") (pinfunction "2_2") (pintype "passive"))
      (node (ref "R32") (pin "1") (pinfunction "1_1") (pintype "passive"))
      (node (ref "R7") (pin "1") (pinfunction "1_1") (pintype "passive"))
      (node (ref "R8") (pin "1") (pinfunction "1_1") (pintype "passive"))
      (node (ref "R9") (pin "1") (pinfunction "1_1") (pintype "passive"))
      (node (ref "SJ6") (pin "2") (pinfunction "2_2") (pintype "passive"))
      (node (ref "SV1") (pin "10") (pinfunction "10_10") (pintype "passive"))
      (node (ref "SV1") (pin "12") (pinfunction "12_12") (pintype "passive"))
      (node (ref "SV1") (pin "14") (pinfunction "14_14") (pintype "passive"))
      (node (ref "SV1") (pin "4") (pinfunction "4_4") (pintype "passive"))
      (node (ref "SV1") (pin "6") (pinfunction "6_6") (pintype "passive"))
      (node (ref "SV1") (pin "8") (pinfunction "8_8") (pintype "passive"))
      (node (ref "SW1") (pin "3") (pinfunction "3_3") (pintype "passive"))
      (node (ref "SW1") (pin "4") (pinfunction "4_4") (pintype "passive"))
      (node (ref "U$1") (pin "P$1") (pinfunction "GND1_P$1") (pintype "passive"))
      (node (ref "U$1") (pin "P$13") (pinfunction "GND_4_P$13") (pintype "passive"))
      (node (ref "U$1") (pin "P$17") (pinfunction "GND_5_P$17") (pintype "passive"))
      (node (ref "U$1") (pin "P$2") (pinfunction "GND2_P$2") (pintype "passive"))
      (node (ref "U$1") (pin "P$24") (pinfunction "GND_6_P$24") (pintype "passive"))
      (node (ref "U$1") (pin "P$3") (pinfunction "GND3_P$3") (pintype "passive"))
      (node (ref "U$1") (pin "P$30") (pinfunction "GND_7_P$30") (pintype "passive"))
      (node (ref "U$1") (pin "P$37") (pinfunction "GND_8_P$37") (pintype "passive"))
      (node (ref "U$1") (pin "P$41") (pinfunction "CRS/CONFIG1_P$41") (pintype "passive"))
      (node (ref "U$2") (pin "P$4") (pinfunction "GND@1_P$4") (pintype "passive"))
      (node (ref "U1") (pin "7") (pinfunction "GND_7") (pintype "passive"))
      (node (ref "U3") (pin "113") (pinfunction "GND@113_113") (pintype "passive"))
      (node (ref "U3") (pin "133") (pinfunction "GND@133_133") (pintype "passive"))
      (node (ref "U3") (pin "14") (pinfunction "GND@14_14") (pintype "passive"))
      (node (ref "U3") (pin "146") (pinfunction "GND@146_146") (pintype "passive"))
      (node (ref "U3") (pin "153") (pinfunction "GNDPLL@153_153") (pintype "passive"))
      (node (ref "U3") (pin "156") (pinfunction "GNDANA_156") (pintype "passive"))
      (node (ref "U3") (pin "170") (pinfunction "GND@170_170") (pintype "passive"))
      (node (ref "U3") (pin "173") (pinfunction "GND@173_173") (pintype "passive"))
      (node (ref "U3") (pin "188") (pinfunction "GND@188_188") (pintype "passive"))
      (node (ref "U3") (pin "200") (pinfunction "GND@200_200") (pintype "passive"))
      (node (ref "U3") (pin "204") (pinfunction "GND@204_204") (pintype "passive"))
      (node (ref "U3") (pin "25") (pinfunction "GND@25_25") (pintype "passive"))
      (node (ref "U3") (pin "33") (pinfunction "GND@33_33") (pintype "passive"))
      (node (ref "U3") (pin "39") (pinfunction "GND@39_39") (pintype "passive"))
      (node (ref "U3") (pin "44") (pinfunction "GNDBU_44") (pintype "passive"))
      (node (ref "U3") (pin "53") (pinfunction "GND@53_53") (pintype "passive"))
      (node (ref "U3") (pin "6") (pinfunction "GND@6_6") (pintype "passive"))
      (node (ref "U3") (pin "66") (pinfunction "GND@66_66") (pintype "passive"))
      (node (ref "U3") (pin "78") (pinfunction "GND@78_78") (pintype "passive"))
      (node (ref "U3") (pin "91") (pinfunction "GND@91_91") (pintype "passive"))
      (node (ref "USD") (pin "6") (pinfunction "VSS_6") (pintype "passive"))
      (node (ref "V7") (pin "0") (pinfunction "GND_0") (pintype "passive"))
      (node (ref "V8") (pin "0") (pinfunction "GND_0") (pintype "passive"))
      (node (ref "VR1") (pin "2") (pinfunction "GND_2") (pintype "passive"))
      (node (ref "VREG1") (pin "1") (pinfunction "GND_1") (pintype "passive"))
      (node (ref "WAKE") (pin "1") (pinfunction "1_1") (pintype "passive"))
      (node (ref "WAKE") (pin "2") (pinfunction "2_2") (pintype "passive"))
      (node (ref "X1") (pin "GND") (pinfunction "GND_GND") (pintype "passive"))
      (node (ref "X2") (pin "GND") (pinfunction "GND_GND") (pintype "passive"))
      (node (ref "X4") (pin "7") (pinfunction "KL_7") (pintype "passive"))
      (node (ref "X4") (pin "8") (pinfunction "KL_8") (pintype "passive"))
    )
    (net (code "6") (name "/LED_A") (class "Default")
      (node (ref "U$1") (pin "P$43") (pinfunction "LED1/SPEED_P$43") (pintype "passive"))
    )
    (net (code "7") (name "/LED_B") (class "Default")
      (node (ref "U$1") (pin "P$42") (pinfunction "LED0/NWAYEN_P$42") (pintype "passive"))
    )
    (net (code "9") (name "/NRST") (class "Default")
      (node (ref "U$1") (pin "P$47") (pinfunction "RST#_P$47") (pintype "passive"))
      (node (ref "U1") (pin "3") (pinfunction "!RST!_3") (pintype "passive"))
      (node (ref "X4") (pin "4") (pinfunction "KL_4") (pintype "passive"))
    )
    (net (code "10") (name "/RD+") (class "Default")
      (node (ref "R24") (pin "1") (pinfunction "1_1") (pintype "passive"))
      (node (ref "U$1") (pin "P$10") (pinfunction "RX+_P$10") (pintype "passive"))
    )
    (net (code "11") (name "/RD-") (class "Default")
      (node (ref "J4") (pin "6") (pinfunction "6_6") (pintype "passive"))
      (node (ref "R10") (pin "1") (pinfunction "1_1") (pintype "passive"))
    )
    (net (code "12") (name "/SHDN") (class "Default")
      (node (ref "R30") (pin "1") (pinfunction "1_1") (pintype "passive"))
      (node (ref "U3") (pin "49") (pinfunction "SHDN_49") (pintype "passive"))
    )
    (net (code "13") (name "/TD+") (class "Default")
      (node (ref "J4") (pin "1") (pinfunction "1_1") (pintype "passive"))
      (node (ref "R28") (pin "1") (pinfunction "1_1") (pintype "passive"))
      (node (ref "U$1") (pin "P$12") (pinfunction "TX+_P$12") (pintype "passive"))
    )
    (net (code "14") (name "/TD-") (class "Default")
      (node (ref "J4") (pin "2") (pinfunction "2_2") (pintype "passive"))
      (node (ref "R26") (pin "1") (pinfunction "1_1") (pintype "passive"))
      (node (ref "U$1") (pin "P$11") (pinfunction "TX-_P$11") (pintype "passive"))
    )
    (net (code "15") (name "/TWCK") (class "Default")
      (node (ref "U3") (pin "1") (pinfunction "PA24/TWCK/ETX3_1") (pintype "passive"))
      (node (ref "X4") (pin "30") (pinfunction "KL_30") (pintype "passive"))
    )
    (net (code "16") (name "/TWD") (class "Default")
      (node (ref "U3") (pin "208") (pinfunction "PA23/TWD/ETX2_208") (pintype "passive"))
      (node (ref "X4") (pin "29") (pinfunction "KL_29") (pintype "passive"))
    )
    (net (code "17") (name "/VDDBU") (class "Default")
      (node (ref "X4") (pin "6") (pinfunction "KL_6") (pintype "passive"))
    )
    (net (code "18") (name "Net-(BATT1-PadV2)") (class "Default")
      (node (ref "BATT1") (pin "V2") (pinfunction "V2_V2") (pintype "passive"))
      (node (ref "R23") (pin "1") (pinfunction "1_1") (pintype "passive"))
    )
    (net (code "19") (name "Net-(C3-Pad2)") (class "Default")
      (node (ref "C3") (pin "2") (pinfunction "2_2") (pintype "passive"))
      (node (ref "R11") (pin "1") (pinfunction "1_1") (pintype "passive"))
      (node (ref "X1") (pin "VBUS") (pinfunction "VBUS_VBUS") (pintype "passive"))
    )
    (net (code "20") (name "Net-(C4-Pad1)") (class "Default")
      (node (ref "C4") (pin "1") (pinfunction "1_1") (pintype "passive"))
      (node (ref "R3") (pin "1") (pinfunction "1_1") (pintype "passive"))
      (node (ref "R7") (pin "2") (pinfunction "2_2") (pintype "passive"))
      (node (ref "X2") (pin "D-") (pinfunction "D-_D-") (pintype "passive"))
    )
    (net (code "21") (name "Net-(C5-Pad1)") (class "Default")
      (node (ref "C5") (pin "1") (pinfunction "1_1") (pintype "passive"))
      (node (ref "R4") (pin "1") (pinfunction "1_1") (pintype "passive"))
      (node (ref "R8") (pin "2") (pinfunction "2_2") (pintype "passive"))
      (node (ref "X2") (pin "D+") (pinfunction "D+_D+") (pintype "passive"))
    )
    (net (code "22") (name "Net-(C31-Pad2)") (class "Default")
      (node (ref "C31") (pin "2") (pinfunction "2_2") (pintype "passive"))
      (node (ref "R20") (pin "2") (pinfunction "2_2") (pintype "passive"))
    )
    (net (code "23") (name "Net-(C75-Pad1)") (class "Default")
      (node (ref "C75") (pin "1") (pinfunction "1_1") (pintype "passive"))
      (node (ref "R10") (pin "2") (pinfunction "2_2") (pintype "passive"))
      (node (ref "R24") (pin "2") (pinfunction "2_2") (pintype "passive"))
    )
    (net (code "24") (name "Net-(F1-Pad1)") (class "Default")
      (node (ref "F1") (pin "1") (pinfunction "1_1") (pintype "passive"))
      (node (ref "X2") (pin "VBUS") (pinfunction "VBUS_VBUS") (pintype "passive"))
    )
    (net (code "25") (name "Net-(IC1-EN)") (class "Default")
      (node (ref "IC1") (pin "5") (pinfunction "EN_5") (pintype "passive"))
      (node (ref "IC4") (pin "7") (pinfunction "SHDN#_7") (pintype "passive"))
      (node (ref "Q2") (pin "3") (pinfunction "D_3") (pintype "passive"))
      (node (ref "R29") (pin "1") (pinfunction "1_1") (pintype "passive"))
    )
    (net (code "26") (name "Net-(IC1-IN)") (class "Default")
      (node (ref "C33") (pin "+") (pinfunction "+_+") (pintype "passive"))
      (node (ref "D1") (pin "C") (pinfunction "C_C") (pintype "passive"))
      (node (ref "IC1") (pin "1") (pinfunction "IN_1") (pintype "passive"))
      (node (ref "R29") (pin "2") (pinfunction "2_2") (pintype "passive"))
      (node (ref "VREG1") (pin "3") (pinfunction "VIN_3") (pintype "passive"))
    )
    (net (code "27") (name "Net-(IC1-OUT)") (class "Default")
      (node (ref "D2") (pin "C") (pinfunction "C_C") (pintype "passive"))
      (node (ref "IC1") (pin "2") (pinfunction "OUT_2") (pintype "passive"))
      (node (ref "U$3") (pin "1") (pinfunction "1_1") (pintype "passive"))
    )
    (net (code "28") (name "Net-(IC2A-!CAS)") (class "Default")
      (node (ref "IC2") (pin "17") (pinfunction "!CAS_17") (pintype "passive"))
      (node (ref "U3") (pin "104") (pinfunction "!CAS_104") (pintype "passive"))
    )
    (net (code "29") (name "Net-(IC2A-!RAS)") (class "Default")
      (node (ref "IC2") (pin "18") (pinfunction "!RAS_18") (pintype "passive"))
      (node (ref "U3") (pin "105") (pinfunction "!RAS_105") (pintype "passive"))
    )
    (net (code "30") (name "Net-(IC2A-!WE)") (class "Default")
      (node (ref "IC2") (pin "16") (pinfunction "!WE_16") (pintype "passive"))
      (node (ref "U3") (pin "116") (pinfunction "!SDWE_116") (pintype "passive"))
    )
    (net (code "31") (name "Net-(IC2A-A0)") (class "Default")
      (node (ref "IC2") (pin "23") (pinfunction "A0_23") (pintype "passive"))
      (node (ref "U3") (pin "98") (pinfunction "NWR2/NBS2/A1_98") (pintype "passive"))
    )
    (net (code "32") (name "Net-(IC2A-A1)") (class "Default")
      (node (ref "IC2") (pin "24") (pinfunction "A1_24") (pintype "passive"))
      (node (ref "U3") (pin "97") (pinfunction "A2_97") (pintype "passive"))
    )
    (net (code "33") (name "Net-(IC2A-A2)") (class "Default")
      (node (ref "IC2") (pin "25") (pinfunction "A2_25") (pintype "passive"))
      (node (ref "U3") (pin "96") (pinfunction "A3_96") (pintype "passive"))
    )
    (net (code "34") (name "Net-(IC2A-A3)") (class "Default")
      (node (ref "IC2") (pin "26") (pinfunction "A3_26") (pintype "passive"))
      (node (ref "U3") (pin "95") (pinfunction "A4_95") (pintype "passive"))
    )
    (net (code "35") (name "Net-(IC2A-A4)") (class "Default")
      (node (ref "IC2") (pin "29") (pinfunction "A4_29") (pintype "passive"))
      (node (ref "U3") (pin "94") (pinfunction "A5_94") (pintype "passive"))
    )
    (net (code "36") (name "Net-(IC2A-A5)") (class "Default")
      (node (ref "IC2") (pin "30") (pinfunction "A5_30") (pintype "passive"))
      (node (ref "U3") (pin "93") (pinfunction "A6_93") (pintype "passive"))
    )
    (net (code "37") (name "Net-(IC2A-A6)") (class "Default")
      (node (ref "IC2") (pin "31") (pinfunction "A6_31") (pintype "passive"))
      (node (ref "U3") (pin "92") (pinfunction "A7_92") (pintype "passive"))
    )
    (net (code "38") (name "Net-(IC2A-A7)") (class "Default")
      (node (ref "IC2") (pin "32") (pinfunction "A7_32") (pintype "passive"))
      (node (ref "U3") (pin "89") (pinfunction "A8_89") (pintype "passive"))
    )
    (net (code "39") (name "Net-(IC2A-A8)") (class "Default")
      (node (ref "IC2") (pin "33") (pinfunction "A8_33") (pintype "passive"))
      (node (ref "U3") (pin "88") (pinfunction "A9_88") (pintype "passive"))
    )
    (net (code "40") (name "Net-(IC2A-A9)") (class "Default")
      (node (ref "IC2") (pin "34") (pinfunction "A9_34") (pintype "passive"))
      (node (ref "U3") (pin "100") (pinfunction "SDA10_100") (pintype "passive"))
    )
    (net (code "41") (name "Net-(IC2A-A10)") (class "Default")
      (node (ref "IC2") (pin "22") (pinfunction "A10_22") (pintype "passive"))
      (node (ref "U3") (pin "86") (pinfunction "A11_86") (pintype "passive"))
    )
    (net (code "42") (name "Net-(IC2A-A11)") (class "Default")
      (node (ref "IC2") (pin "35") (pinfunction "A11_35") (pintype "passive"))
      (node (ref "U3") (pin "85") (pinfunction "A12_85") (pintype "passive"))
    )
    (net (code "43") (name "Net-(IC2A-A12)") (class "Default")
      (node (ref "IC2") (pin "36") (pinfunction "A12_36") (pintype "passive"))
      (node (ref "R31") (pin "1") (pinfunction "1_1") (pintype "passive"))
    )
    (net (code "44") (name "Net-(IC2A-BA0)") (class "Default")
      (node (ref "IC2") (pin "20") (pinfunction "BA0_20") (pintype "passive"))
      (node (ref "U3") (pin "81") (pinfunction "BA0/A16_81") (pintype "passive"))
    )
    (net (code "45") (name "Net-(IC2A-BA1)") (class "Default")
      (node (ref "IC2") (pin "21") (pinfunction "BA1_21") (pintype "passive"))
      (node (ref "U3") (pin "80") (pinfunction "BA1/A17_80") (pintype "passive"))
    )
    (net (code "46") (name "Net-(IC2A-CKE)") (class "Default")
      (node (ref "IC2") (pin "37") (pinfunction "CKE_37") (pintype "passive"))
      (node (ref "U3") (pin "117") (pinfunction "SDCKE_117") (pintype "passive"))
    )
    (net (code "47") (name "Net-(IC2A-CLK)") (class "Default")
      (node (ref "IC2") (pin "38") (pinfunction "CLK_38") (pintype "passive"))
      (node (ref "U3") (pin "115") (pinfunction "SDCK_115") (pintype "passive"))
    )
    (net (code "48") (name "Net-(IC2A-CS)") (class "Default")
      (node (ref "IC2") (pin "19") (pinfunction "CS_19") (pintype "passive"))
      (node (ref "R6") (pin "2") (pinfunction "2_2") (pintype "passive"))
      (node (ref "U3") (pin "103") (pinfunction "SDCS/NCS1_103") (pintype "passive"))
    )
    (net (code "49") (name "Net-(IC2A-DQMH)") (class "Default")
      (node (ref "IC2") (pin "39") (pinfunction "DQMH_39") (pintype "passive"))
      (node (ref "U3") (pin "102") (pinfunction "CFIOR/NBS1/NWR1_102") (pintype "passive"))
    )
    (net (code "50") (name "Net-(IC2A-DQML)") (class "Default")
      (node (ref "IC2") (pin "15") (pinfunction "DQML_15") (pintype "passive"))
      (node (ref "U3") (pin "99") (pinfunction "NBS0/A0_99") (pintype "passive"))
    )
    (net (code "51") (name "Net-(IC4-C+)") (class "Default")
      (node (ref "C43") (pin "2") (pinfunction "2_2") (pintype "passive"))
      (node (ref "IC4") (pin "6") (pinfunction "C+_6") (pintype "passive"))
    )
    (net (code "52") (name "Net-(IC4-C-)") (class "Default")
      (node (ref "C43") (pin "1") (pinfunction "1_1") (pintype "passive"))
      (node (ref "IC4") (pin "5") (pinfunction "C-_5") (pintype "passive"))
    )
    (net (code "53") (name "Net-(IC4-FB)") (class "Default")
      (node (ref "IC4") (pin "8") (pinfunction "FB_8") (pintype "passive"))
      (node (ref "R32") (pin "2") (pinfunction "2_2") (pintype "passive"))
      (node (ref "R33") (pin "2") (pinfunction "2_2") (pintype "passive"))
    )
    (net (code "54") (name "Net-(IC4-PGOOD)") (class "Default")
      (node (ref "IC4") (pin "1") (pinfunction "PGOOD_1") (pintype "passive"))
      (node (ref "R34") (pin "1") (pinfunction "1_1") (pintype "passive"))
    )
    (net (code "55") (name "Net-(J4-Pad4)") (class "Default")
      (node (ref "J4") (pin "4") (pinfunction "4_4") (pintype "passive"))
      (node (ref "J4") (pin "5") (pinfunction "5_5") (pintype "passive"))
    )
    (net (code "56") (name "Net-(J4-Pad10)") (class "Default")
      (node (ref "J4") (pin "10") (pinfunction "10_10") (pintype "passive"))
      (node (ref "R4A") (pin "2") (pinfunction "2_2") (pintype "passive"))
    )
    (net (code "57") (name "Net-(J4-Pad11)") (class "Default")
      (node (ref "J4") (pin "11") (pinfunction "11_11") (pintype "passive"))
      (node (ref "R5A") (pin "2") (pinfunction "2_2") (pintype "passive"))
    )
    (net (code "58") (name "Net-(L2-1)") (class "Default")
      (node (ref "C12") (pin "2") (pinfunction "2_2") (pintype "passive"))
      (node (ref "C26") (pin "2") (pinfunction "2_2") (pintype "passive"))
      (node (ref "L2") (pin "2") (pinfunction "1_2") (pintype "passive"))
      (node (ref "U$1") (pin "P$7") (pinfunction "VDDA_3.3_1_P$7") (pintype "passive"))
      (node (ref "U$1") (pin "P$8") (pinfunction "VDDA_3.3_2_P$8") (pintype "passive"))
    )
    (net (code "59") (name "Net-(L3-1)") (class "Default")
      (node (ref "C36") (pin "1") (pinfunction "1_1") (pintype "passive"))
      (node (ref "C52") (pin "1") (pinfunction "1_1") (pintype "passive"))
      (node (ref "L3") (pin "2") (pinfunction "1_2") (pintype "passive"))
      (node (ref "L4") (pin "2") (pinfunction "1_2") (pintype "passive"))
      (node (ref "U$1") (pin "P$6") (pinfunction "V1.8_OUT_P$6") (pintype "passive"))
    )
    (net (code "60") (name "Net-(L3-2)") (class "Default")
      (node (ref "C55") (pin "1") (pinfunction "1_1") (pintype "passive"))
      (node (ref "C56") (pin "1") (pinfunction "1_1") (pintype "passive"))
      (node (ref "L3") (pin "1") (pinfunction "2_1") (pintype "passive"))
      (node (ref "U$1") (pin "P$4") (pinfunction "VDDA_1.8_1_P$4") (pintype "passive"))
      (node (ref "U$1") (pin "P$5") (pinfunction "VDDA_1.8_2_P$5") (pintype "passive"))
    )
    (net (code "61") (name "Net-(L4-2)") (class "Default")
      (node (ref "C57") (pin "2") (pinfunction "2_2") (pintype "passive"))
      (node (ref "L4") (pin "1") (pinfunction "2_1") (pintype "passive"))
      (node (ref "U$1") (pin "P$31") (pinfunction "VDD_1.8_3_P$31") (pintype "passive"))
    )
    (net (code "62") (name "Net-(LED1-PadC)") (class "Default")
      (node (ref "LED1") (pin "C") (pinfunction "C_C") (pintype "passive"))
      (node (ref "R16") (pin "1") (pinfunction "1_1") (pintype "passive"))
    )
    (net (code "63") (name "Net-(LED2-PadC)") (class "Default")
      (node (ref "LED2") (pin "C") (pinfunction "C_C") (pintype "passive"))
      (node (ref "R17") (pin "1") (pinfunction "1_1") (pintype "passive"))
    )
    (net (code "64") (name "Net-(LED3-PadC)") (class "Default")
      (node (ref "LED3") (pin "C") (pinfunction "C_C") (pintype "passive"))
      (node (ref "R22") (pin "1") (pinfunction "1_1") (pintype "passive"))
    )
    (net (code "65") (name "Net-(LINK/ACT-PadC)") (class "Default")
      (node (ref "LINK/ACT") (pin "C") (pinfunction "C_C") (pintype "passive"))
      (node (ref "R35") (pin "2") (pinfunction "2_2") (pintype "passive"))
    )
    (net (code "66") (name "Net-(Q2-G)") (class "Default")
      (node (ref "C32") (pin "2") (pinfunction "2_2") (pintype "passive"))
      (node (ref "Q2") (pin "1") (pinfunction "G_1") (pintype "passive"))
      (node (ref "R30") (pin "2") (pinfunction "2_2") (pintype "passive"))
    )
    (net (code "67") (name "Net-(R1-Pad1)") (class "Default")
      (node (ref "R1") (pin "1") (pinfunction "1_1") (pintype "passive"))
      (node (ref "X1") (pin "D+") (pinfunction "D+_D+") (pintype "passive"))
    )
    (net (code "68") (name "Net-(R2-Pad1)") (class "Default")
      (node (ref "R2") (pin "1") (pinfunction "1_1") (pintype "passive"))
      (node (ref "X1") (pin "D-") (pinfunction "D-_D-") (pintype "passive"))
    )
    (net (code "69") (name "Net-(R36-Pad2)") (class "Default")
      (node (ref "R36") (pin "2") (pinfunction "2_2") (pintype "passive"))
      (node (ref "SPEED") (pin "C") (pinfunction "C_C") (pintype "passive"))
    )
    (net (code "70") (name "Net-(RN2B-1)") (class "Default")
      (node (ref "RN2") (pin "2") (pinfunction "1_2") (pintype "passive"))
      (node (ref "SV1") (pin "7") (pinfunction "7_7") (pintype "passive"))
      (node (ref "U3") (pin "31") (pinfunction "TMS_31") (pintype "passive"))
    )
    (net (code "71") (name "Net-(RN2C-1)") (class "Default")
      (node (ref "RN2") (pin "3") (pinfunction "1_3") (pintype "passive"))
      (node (ref "SV1") (pin "5") (pinfunction "5_5") (pintype "passive"))
      (node (ref "U3") (pin "30") (pinfunction "TDI_30") (pintype "passive"))
    )
    (net (code "72") (name "Net-(RN2D-1)") (class "Default")
      (node (ref "RN2") (pin "4") (pinfunction "1_4") (pintype "passive"))
      (node (ref "SV1") (pin "3") (pinfunction "3_3") (pintype "passive"))
      (node (ref "U3") (pin "35") (pinfunction "NTRST_35") (pintype "passive"))
    )
    (net (code "73") (name "Net-(U$1-REXT)") (class "Default")
      (node (ref "C61") (pin "2") (pinfunction "2_2") (pintype "passive"))
      (node (ref "R15") (pin "1") (pinfunction "1_1") (pintype "passive"))
      (node (ref "U$1") (pin "P$16") (pinfunction "REXT_P$16") (pintype "passive"))
    )
    (net (code "74") (name "Net-(U$1-RXD0{slash}RXD[0]{slash}RX_DUPLEX)") (class "Default")
      (node (ref "U$1") (pin "P$23") (pinfunction "RXD0/RXD[0]/RX_DUPLEX_P$23") (pintype "passive"))
      (node (ref "U3") (pin "195") (pinfunction "PA14/ERX0_195") (pintype "passive"))
    )
    (net (code "75") (name "Net-(U$1-RXD1{slash}RXD[1]{slash}PHYAD02)") (class "Default")
      (node (ref "U$1") (pin "P$22") (pinfunction "RXD1/RXD[1]/PHYAD02_P$22") (pintype "passive"))
      (node (ref "U3") (pin "196") (pinfunction "PA15/ERX1_196") (pintype "passive"))
    )
    (net (code "76") (name "Net-(U$1-RXDV{slash}CRSDV{slash}CONFIG2)") (class "Default")
      (node (ref "R9") (pin "2") (pinfunction "2_2") (pintype "passive"))
      (node (ref "U$1") (pin "P$27") (pinfunction "RXDV/CRSDV/CONFIG2_P$27") (pintype "passive"))
      (node (ref "U3") (pin "198") (pinfunction "PA17/ERXDV_198") (pintype "passive"))
    )
    (net (code "77") (name "Net-(U$1-RXER{slash}RX_ER{slash}ISO)") (class "Default")
      (node (ref "U$1") (pin "P$29") (pinfunction "RXER/RX_ER/ISO_P$29") (pintype "passive"))
      (node (ref "U3") (pin "201") (pinfunction "PA18/ERXER_201") (pintype "passive"))
    )
    (net (code "78") (name "Net-(U$1-TXD0{slash}TXD[0]{slash}TX)") (class "Default")
      (node (ref "U$1") (pin "P$35") (pinfunction "TXD0/TXD[0]/TX_P$35") (pintype "passive"))
      (node (ref "U3") (pin "193") (pinfunction "PA12/ETX0_193") (pintype "passive"))
    )
    (net (code "79") (name "Net-(U$1-TXD1{slash}TXD[1]{slash}SYNC)") (class "Default")
      (node (ref "U$1") (pin "P$36") (pinfunction "TXD1/TXD[1]/SYNC_P$36") (pintype "passive"))
      (node (ref "U3") (pin "194") (pinfunction "PA13/ETX1_194") (pintype "passive"))
    )
    (net (code "80") (name "Net-(U$1-TXEN{slash}TX_EN)") (class "Default")
      (node (ref "U$1") (pin "P$34") (pinfunction "TXEN/TX_EN_P$34") (pintype "passive"))
      (node (ref "U3") (pin "197") (pinfunction "PA16/ETXEN_197") (pintype "passive"))
    )
    (net (code "81") (name "Net-(U$1-XI{slash}REFCLK{slash}CLOCK)") (class "Default")
      (node (ref "U$1") (pin "P$15") (pinfunction "XI/REFCLK/CLOCK_P$15") (pintype "passive"))
      (node (ref "U3") (pin "202") (pinfunction "PA19/ETXCK_202") (pintype "passive"))
    )
    (net (code "82") (name "Net-(U$2-PWR)") (class "Default")
      (node (ref "D1") (pin "A") (pinfunction "A_A") (pintype "passive"))
      (node (ref "U$2") (pin "VIN0") (pinfunction "PWR_VIN0") (pintype "passive"))
    )
    (net (code "83") (name "Net-(U1-!CS!)") (class "Default")
      (node (ref "R5") (pin "1") (pinfunction "1_1") (pintype "passive"))
      (node (ref "U1") (pin "4") (pinfunction "!CS!_4") (pintype "passive"))
      (node (ref "U3") (pin "182") (pinfunction "PA3/SPI0_NPCS0/MCDB3_182") (pintype "passive"))
    )
    (net (code "84") (name "Net-(U1-!WP!)") (class "Default")
      (node (ref "SJ6") (pin "1") (pinfunction "1_1") (pintype "passive"))
      (node (ref "U1") (pin "5") (pinfunction "!WP!_5") (pintype "passive"))
    )
    (net (code "85") (name "Net-(U1-SCK)") (class "Default")
      (node (ref "U1") (pin "2") (pinfunction "SCK_2") (pintype "passive"))
      (node (ref "U3") (pin "181") (pinfunction "PA2/SPI0_SPCK_181") (pintype "passive"))
    )
    (net (code "86") (name "Net-(U1-SI)") (class "Default")
      (node (ref "U1") (pin "1") (pinfunction "SI_1") (pintype "passive"))
      (node (ref "U3") (pin "180") (pinfunction "PA1/SPI0_MOSI/MCCDB_180") (pintype "passive"))
    )
    (net (code "87") (name "Net-(U1-SO)") (class "Default")
      (node (ref "U1") (pin "8") (pinfunction "SO_8") (pintype "passive"))
      (node (ref "U3") (pin "179") (pinfunction "PA0/SPI0_MISO/MCDB0_179") (pintype "passive"))
    )
    (net (code "88") (name "Net-(U3-A13)") (class "Default")
      (node (ref "R31") (pin "2") (pinfunction "2_2") (pintype "passive"))
      (node (ref "U3") (pin "84") (pinfunction "A13_84") (pintype "passive"))
    )
    (net (code "89") (name "Net-(U3-BMS)") (class "Default")
      (node (ref "R25") (pin "2") (pinfunction "2_2") (pintype "passive"))
      (node (ref "U3") (pin "40") (pinfunction "BMS_40") (pintype "passive"))
    )
    (net (code "90") (name "Net-(U3-D14)") (class "Default")
      (node (ref "U3") (pin "125") (pinfunction "D14_125") (pintype "passive"))
      (node (ref "U3") (pin "126") (pinfunction "D15_126") (pintype "passive"))
    )
    (net (code "91") (name "Net-(U3-D29{slash}PC29)") (class "Default")
      (node (ref "LED3") (pin "A") (pinfunction "A_A") (pintype "passive"))
      (node (ref "U3") (pin "143") (pinfunction "D29/PC29_143") (pintype "passive"))
    )
    (net (code "92") (name "Net-(U3-D30{slash}PC30)") (class "Default")
      (node (ref "LED2") (pin "A") (pinfunction "A_A") (pintype "passive"))
      (node (ref "U3") (pin "144") (pinfunction "D30/PC30_144") (pintype "passive"))
    )
    (net (code "93") (name "Net-(U3-D31{slash}PC31)") (class "Default")
      (node (ref "LED1") (pin "A") (pinfunction "A_A") (pintype "passive"))
      (node (ref "U3") (pin "145") (pinfunction "D31/PC31_145") (pintype "passive"))
    )
    (net (code "94") (name "Net-(U3-DDM)") (class "Default")
      (node (ref "C1") (pin "2") (pinfunction "2_2") (pintype "passive"))
      (node (ref "R2") (pin "2") (pinfunction "2_2") (pintype "passive"))
      (node (ref "U3") (pin "54") (pinfunction "DDM_54") (pintype "passive"))
    )
    (net (code "95") (name "Net-(U3-DDP)") (class "Default")
      (node (ref "C2") (pin "2") (pinfunction "2_2") (pintype "passive"))
      (node (ref "R1") (pin "2") (pinfunction "2_2") (pintype "passive"))
      (node (ref "U3") (pin "55") (pinfunction "DDP_55") (pintype "passive"))
    )
    (net (code "96") (name "Net-(U3-DRXD{slash}PB14)") (class "Default")
      (node (ref "U3") (pin "21") (pinfunction "DRXD/PB14_21") (pintype "passive"))
      (node (ref "X4") (pin "5") (pinfunction "KL_5") (pintype "passive"))
    )
    (net (code "97") (name "Net-(U3-DTXD{slash}PB15)") (class "Default")
      (node (ref "U3") (pin "22") (pinfunction "DTXD/PB15_22") (pintype "passive"))
      (node (ref "X4") (pin "3") (pinfunction "KL_3") (pintype "passive"))
    )
    (net (code "98") (name "Net-(U3-GNDPLL@151)") (class "Default")
      (node (ref "C29") (pin "2") (pinfunction "2_2") (pintype "passive"))
      (node (ref "U3") (pin "151") (pinfunction "GNDPLL@151_151") (pintype "passive"))
    )
    (net (code "99") (name "Net-(U3-HDMA)") (class "Default")
      (node (ref "R3") (pin "2") (pinfunction "2_2") (pintype "passive"))
      (node (ref "U3") (pin "50") (pinfunction "HDMA_50") (pintype "passive"))
    )
    (net (code "100") (name "Net-(U3-HDPA)") (class "Default")
      (node (ref "R4") (pin "2") (pinfunction "2_2") (pintype "passive"))
      (node (ref "U3") (pin "51") (pinfunction "HDPA_51") (pintype "passive"))
    )
    (net (code "101") (name "Net-(U3-IRQ1{slash}NWAIT{slash}PC15)") (class "Default")
      (node (ref "U3") (pin "127") (pinfunction "IRQ1/NWAIT/PC15_127") (pintype "passive"))
      (node (ref "X4") (pin "12") (pinfunction "KL_12") (pintype "passive"))
    )
    (net (code "102") (name "Net-(U3-IRQ2{slash}NCS3_NANDCS{slash}PC14)") (class "Default")
      (node (ref "U3") (pin "59") (pinfunction "IRQ2/NCS3_NANDCS/PC14_59") (pintype "passive"))
      (node (ref "X4") (pin "16") (pinfunction "KL_16") (pintype "passive"))
    )
    (net (code "103") (name "Net-(U3-JTAGSEL)") (class "Default")
      (node (ref "SJ3") (pin "2") (pinfunction "2_2") (pintype "passive"))
      (node (ref "U3") (pin "43") (pinfunction "JTAGSEL_43") (pintype "passive"))
    )
    (net (code "104") (name "Net-(U3-NRST)") (class "Default")
      (node (ref "C34") (pin "1") (pinfunction "1_1") (pintype "passive"))
      (node (ref "R27") (pin "2") (pinfunction "2_2") (pintype "passive"))
      (node (ref "SW1") (pin "1") (pinfunction "1_1") (pintype "passive"))
      (node (ref "SW1") (pin "2") (pinfunction "2_2") (pintype "passive"))
      (node (ref "U3") (pin "36") (pinfunction "NRST_36") (pintype "passive"))
    )
    (net (code "105") (name "Net-(U3-OSCSEL)") (class "Default")
      (node (ref "R19") (pin "1") (pinfunction "1_1") (pintype "passive"))
      (node (ref "U3") (pin "41") (pinfunction "OSCSEL_41") (pintype "passive"))
    )
    (net (code "106") (name "Net-(U3-PA6{slash}MCDA0)") (class "Default")
      (node (ref "U3") (pin "185") (pinfunction "PA6/MCDA0_185") (pintype "passive"))
      (node (ref "USD") (pin "7") (pinfunction "DO_7") (pintype "passive"))
    )
    (net (code "107") (name "Net-(U3-PA7{slash}MCCDA)") (class "Default")
      (node (ref "U3") (pin "186") (pinfunction "PA7/MCCDA_186") (pintype "passive"))
      (node (ref "USD") (pin "3") (pinfunction "DI_3") (pintype "passive"))
    )
    (net (code "108") (name "Net-(U3-PA8{slash}MCCK)") (class "Default")
      (node (ref "R13") (pin "1") (pinfunction "1_1") (pintype "passive"))
      (node (ref "U3") (pin "189") (pinfunction "PA8/MCCK_189") (pintype "passive"))
      (node (ref "USD") (pin "5") (pinfunction "SCLK_5") (pintype "passive"))
    )
    (net (code "109") (name "Net-(U3-PA9{slash}MCDA1)") (class "Default")
      (node (ref "U3") (pin "190") (pinfunction "PA9/MCDA1_190") (pintype "passive"))
      (node (ref "USD") (pin "8") (pinfunction "DATA1_8") (pintype "passive"))
    )
    (net (code "110") (name "Net-(U3-PA10{slash}MCDA2{slash}ETX2)") (class "Default")
      (node (ref "U3") (pin "191") (pinfunction "PA10/MCDA2/ETX2_191") (pintype "passive"))
      (node (ref "USD") (pin "1") (pinfunction "DATA2_1") (pintype "passive"))
    )
    (net (code "111") (name "Net-(U3-PA11{slash}MCDA3{slash}ETX3)") (class "Default")
      (node (ref "U3") (pin "192") (pinfunction "PA11/MCDA3/ETX3_192") (pintype "passive"))
      (node (ref "USD") (pin "2") (pinfunction "CS_2") (pintype "passive"))
    )
    (net (code "112") (name "Net-(U3-PA26{slash}TIOA0{slash}ERX3)") (class "Default")
      (node (ref "R11") (pin "2") (pinfunction "2_2") (pintype "passive"))
      (node (ref "R12") (pin "1") (pinfunction "1_1") (pintype "passive"))
      (node (ref "U3") (pin "3") (pinfunction "PA26/TIOA0/ERX3_3") (pintype "passive"))
    )
    (net (code "113") (name "Net-(U3-PCK0{slash}AD1{slash}PC1)") (class "Default")
      (node (ref "U3") (pin "159") (pinfunction "PCK0/AD1/PC1_159") (pintype "passive"))
      (node (ref "X4") (pin "9") (pinfunction "KL_9") (pintype "passive"))
    )
    (net (code "114") (name "Net-(U3-PLLRCA)") (class "Default")
      (node (ref "C30") (pin "2") (pinfunction "2_2") (pintype "passive"))
      (node (ref "R20") (pin "1") (pinfunction "1_1") (pintype "passive"))
      (node (ref "U3") (pin "154") (pinfunction "PLLRCA_154") (pintype "passive"))
    )
    (net (code "115") (name "Net-(U3-RTCK)") (class "Default")
      (node (ref "SV1") (pin "11") (pinfunction "11_11") (pintype "passive"))
      (node (ref "U3") (pin "37") (pinfunction "RTCK_37") (pintype "passive"))
    )
    (net (code "116") (name "Net-(U3-RXD0{slash}PB5)") (class "Default")
      (node (ref "U3") (pin "16") (pinfunction "RXD0/PB5_16") (pintype "passive"))
      (node (ref "X4") (pin "23") (pinfunction "KL_23") (pintype "passive"))
    )
    (net (code "117") (name "Net-(U3-RXD2{slash}PB9)") (class "Default")
      (node (ref "U3") (pin "20") (pinfunction "RXD2/PB9_20") (pintype "passive"))
      (node (ref "X4") (pin "19") (pinfunction "KL_19") (pintype "passive"))
    )
    (net (code "118") (name "Net-(U3-SCK3{slash}AD0{slash}PC0)") (class "Default")
      (node (ref "U3") (pin "158") (pinfunction "SCK3/AD0/PC0_158") (pintype "passive"))
      (node (ref "X4") (pin "10") (pinfunction "KL_10") (pintype "passive"))
    )
    (net (code "119") (name "Net-(U3-SPI1_NPCS1{slash}A24{slash}PC5)") (class "Default")
      (node (ref "U3") (pin "67") (pinfunction "SPI1_NPCS1/A24/PC5_67") (pintype "passive"))
      (node (ref "X4") (pin "14") (pinfunction "KL_14") (pintype "passive"))
    )
    (net (code "120") (name "Net-(U3-SPI1_NPCS2{slash}A23{slash}PC4)") (class "Default")
      (node (ref "U3") (pin "62") (pinfunction "SPI1_NPCS2/A23/PC4_62") (pintype "passive"))
      (node (ref "X4") (pin "15") (pinfunction "KL_15") (pintype "passive"))
    )
    (net (code "121") (name "Net-(U3-TCK)") (class "Default")
      (node (ref "RN2") (pin "1") (pinfunction "1_1") (pintype "passive"))
      (node (ref "SV1") (pin "9") (pinfunction "9_9") (pintype "passive"))
      (node (ref "U3") (pin "34") (pinfunction "TCK_34") (pintype "passive"))
    )
    (net (code "122") (name "Net-(U3-TCLK1{slash}TXD1{slash}PB6)") (class "Default")
      (node (ref "U3") (pin "17") (pinfunction "TCLK1/TXD1/PB6_17") (pintype "passive"))
      (node (ref "X4") (pin "22") (pinfunction "KL_22") (pintype "passive"))
    )
    (net (code "123") (name "Net-(U3-TCLK2{slash}RXD1{slash}PB7)") (class "Default")
      (node (ref "U3") (pin "18") (pinfunction "TCLK2/RXD1/PB7_18") (pintype "passive"))
      (node (ref "X4") (pin "21") (pinfunction "KL_21") (pintype "passive"))
    )
    (net (code "124") (name "Net-(U3-TCLK3{slash}TK0{slash}PB16)") (class "Default")
      (node (ref "U3") (pin "23") (pinfunction "TCLK3/TK0/PB16_23") (pintype "passive"))
      (node (ref "X4") (pin "18") (pinfunction "KL_18") (pintype "passive"))
    )
    (net (code "125") (name "Net-(U3-TCLK4{slash}TF0{slash}PB17)") (class "Default")
      (node (ref "U3") (pin "26") (pinfunction "TCLK4/TF0/PB17_26") (pintype "passive"))
      (node (ref "X4") (pin "17") (pinfunction "KL_17") (pintype "passive"))
    )
    (net (code "126") (name "Net-(U3-TDO)") (class "Default")
      (node (ref "SV1") (pin "13") (pinfunction "13_13") (pintype "passive"))
      (node (ref "U3") (pin "29") (pinfunction "TDO_29") (pintype "passive"))
    )
    (net (code "127") (name "Net-(U3-TIOA3{slash}SPI1_MISO{slash}PB0)") (class "Default")
      (node (ref "U3") (pin "9") (pinfunction "TIOA3/SPI1_MISO/PB0_9") (pintype "passive"))
      (node (ref "X4") (pin "28") (pinfunction "KL_28") (pintype "passive"))
    )
    (net (code "128") (name "Net-(U3-TIOA4{slash}SPI1_SPCK{slash}PB2)") (class "Default")
      (node (ref "U3") (pin "11") (pinfunction "TIOA4/SPI1_SPCK/PB2_11") (pintype "passive"))
      (node (ref "X4") (pin "26") (pinfunction "KL_26") (pintype "passive"))
    )
    (net (code "129") (name "Net-(U3-TIOA5{slash}SPI1_NPCS0{slash}PB3)") (class "Default")
      (node (ref "U3") (pin "12") (pinfunction "TIOA5/SPI1_NPCS0/PB3_12") (pintype "passive"))
      (node (ref "X4") (pin "25") (pinfunction "KL_25") (pintype "passive"))
    )
    (net (code "130") (name "Net-(U3-TIOB3{slash}SPI1_MOSI{slash}PB1)") (class "Default")
      (node (ref "U3") (pin "10") (pinfunction "TIOB3/SPI1_MOSI/PB1_10") (pintype "passive"))
      (node (ref "X4") (pin "27") (pinfunction "KL_27") (pintype "passive"))
    )
    (net (code "131") (name "Net-(U3-TIOB4{slash}TD0{slash}PB18)") (class "Default")
      (node (ref "U3") (pin "27") (pinfunction "TIOB4/TD0/PB18_27") (pintype "passive"))
      (node (ref "X4") (pin "13") (pinfunction "KL_13") (pintype "passive"))
    )
    (net (code "132") (name "Net-(U3-TIOB5{slash}RD0{slash}PB19)") (class "Default")
      (node (ref "U3") (pin "28") (pinfunction "TIOB5/RD0/PB19_28") (pintype "passive"))
      (node (ref "X4") (pin "11") (pinfunction "KL_11") (pintype "passive"))
    )
    (net (code "133") (name "Net-(U3-TST)") (class "Default")
      (node (ref "R14") (pin "2") (pinfunction "2_2") (pintype "passive"))
      (node (ref "U3") (pin "42") (pinfunction "TST_42") (pintype "passive"))
    )
    (net (code "134") (name "Net-(U3-TXD0{slash}PB4)") (class "Default")
      (node (ref "U3") (pin "15") (pinfunction "TXD0/PB4_15") (pintype "passive"))
      (node (ref "X4") (pin "24") (pinfunction "KL_24") (pintype "passive"))
    )
    (net (code "135") (name "Net-(U3-TXD2{slash}PB8)") (class "Default")
      (node (ref "U3") (pin "19") (pinfunction "TXD2/PB8_19") (pintype "passive"))
      (node (ref "X4") (pin "20") (pinfunction "KL_20") (pintype "passive"))
    )
    (net (code "136") (name "Net-(U3-VDDBU)") (class "Default")
      (node (ref "C27") (pin "1") (pinfunction "1_1") (pintype "passive"))
      (node (ref "C35") (pin "2") (pinfunction "2_2") (pintype "passive"))
      (node (ref "R19") (pin "2") (pinfunction "2_2") (pintype "passive"))
      (node (ref "R21") (pin "2") (pinfunction "2_2") (pintype "passive"))
      (node (ref "U3") (pin "47") (pinfunction "VDDBU_47") (pintype "passive"))
      (node (ref "VR1") (pin "5") (pinfunction "OUT_5") (pintype "passive"))
    )
    (net (code "137") (name "Net-(U3-WKUP)") (class "Default")
      (node (ref "R21") (pin "1") (pinfunction "1_1") (pintype "passive"))
      (node (ref "U3") (pin "48") (pinfunction "WKUP_48") (pintype "passive"))
      (node (ref "WAKE") (pin "3") (pinfunction "3_3") (pintype "passive"))
      (node (ref "WAKE") (pin "4") (pinfunction "4_4") (pintype "passive"))
    )
    (net (code "138") (name "Net-(U3-XIN)") (class "Default")
      (node (ref "C9") (pin "2") (pinfunction "2_2") (pintype "passive"))
      (node (ref "U3") (pin "149") (pinfunction "XIN_149") (pintype "passive"))
      (node (ref "X3") (pin "1") (pinfunction "X1_1") (pintype "passive"))
    )
    (net (code "139") (name "Net-(U3-XIN32)") (class "Default")
      (node (ref "C11") (pin "2") (pinfunction "2_2") (pintype "passive"))
      (node (ref "Q1") (pin "1") (pinfunction "1_1") (pintype "passive"))
      (node (ref "U3") (pin "46") (pinfunction "XIN32_46") (pintype "passive"))
    )
    (net (code "140") (name "Net-(U3-XOUT)") (class "Default")
      (node (ref "C8") (pin "2") (pinfunction "2_2") (pintype "passive"))
      (node (ref "U3") (pin "150") (pinfunction "XOUT_150") (pintype "passive"))
      (node (ref "X3") (pin "2") (pinfunction "X2_2") (pintype "passive"))
    )
    (net (code "141") (name "Net-(U3-XOUT32)") (class "Default")
      (node (ref "C10") (pin "2") (pinfunction "2_2") (pintype "passive"))
      (node (ref "Q1") (pin "2") (pinfunction "2_2") (pintype "passive"))
      (node (ref "U3") (pin "45") (pinfunction "XOUT32_45") (pintype "passive"))
    )
    (net (code "142") (name "Net-(VR1-EN)") (class "Default")
      (node (ref "R23") (pin "2") (pinfunction "2_2") (pintype "passive"))
      (node (ref "VR1") (pin "1") (pinfunction "IN_1") (pintype "passive"))
      (node (ref "VR1") (pin "3") (pinfunction "EN_3") (pintype "passive"))
    )
    (net (code "143") (name "unconnected-(BATT1-PadV1)") (class "Default")
      (node (ref "BATT1") (pin "V1") (pinfunction "V1_V1") (pintype "passive"))
    )
    (net (code "144") (name "unconnected-(IC2A-DQ0-Pad2)") (class "Default")
      (node (ref "IC2") (pin "2") (pinfunction "DQ0_2") (pintype "passive"))
    )
    (net (code "145") (name "unconnected-(IC2A-DQ1-Pad4)") (class "Default")
      (node (ref "IC2") (pin "4") (pinfunction "DQ1_4") (pintype "passive"))
    )
    (net (code "146") (name "unconnected-(IC2A-DQ2-Pad5)") (class "Default")
      (node (ref "IC2") (pin "5") (pinfunction "DQ2_5") (pintype "passive"))
    )
    (net (code "147") (name "unconnected-(IC2A-DQ3-Pad7)") (class "Default")
      (node (ref "IC2") (pin "7") (pinfunction "DQ3_7") (pintype "passive"))
    )
    (net (code "148") (name "unconnected-(IC2A-DQ4-Pad8)") (class "Default")
      (node (ref "IC2") (pin "8") (pinfunction "DQ4_8") (pintype "passive"))
    )
    (net (code "149") (name "unconnected-(IC2A-DQ5-Pad10)") (class "Default")
      (node (ref "IC2") (pin "10") (pinfunction "DQ5_10") (pintype "passive"))
    )
    (net (code "150") (name "unconnected-(IC2A-DQ6-Pad11)") (class "Default")
      (node (ref "IC2") (pin "11") (pinfunction "DQ6_11") (pintype "passive"))
    )
    (net (code "151") (name "unconnected-(IC2A-DQ7-Pad13)") (class "Default")
      (node (ref "IC2") (pin "13") (pinfunction "DQ7_13") (pintype "passive"))
    )
    (net (code "152") (name "unconnected-(IC2A-DQ8-Pad42)") (class "Default")
      (node (ref "IC2") (pin "42") (pinfunction "DQ8_42") (pintype "passive"))
    )
    (net (code "153") (name "unconnected-(IC2A-DQ9-Pad44)") (class "Default")
      (node (ref "IC2") (pin "44") (pinfunction "DQ9_44") (pintype "passive"))
    )
    (net (code "154") (name "unconnected-(IC2A-DQ10-Pad45)") (class "Default")
      (node (ref "IC2") (pin "45") (pinfunction "DQ10_45") (pintype "passive"))
    )
    (net (code "155") (name "unconnected-(IC2A-DQ11-Pad47)") (class "Default")
      (node (ref "IC2") (pin "47") (pinfunction "DQ11_47") (pintype "passive"))
    )
    (net (code "156") (name "unconnected-(IC2A-DQ12-Pad48)") (class "Default")
      (node (ref "IC2") (pin "48") (pinfunction "DQ12_48") (pintype "passive"))
    )
    (net (code "157") (name "unconnected-(IC2A-DQ13-Pad50)") (class "Default")
      (node (ref "IC2") (pin "50") (pinfunction "DQ13_50") (pintype "passive"))
    )
    (net (code "158") (name "unconnected-(IC2A-DQ14-Pad51)") (class "Default")
      (node (ref "IC2") (pin "51") (pinfunction "DQ14_51") (pintype "passive"))
    )
    (net (code "159") (name "unconnected-(IC2A-DQ15-Pad53)") (class "Default")
      (node (ref "IC2") (pin "53") (pinfunction "DQ15_53") (pintype "passive"))
    )
    (net (code "160") (name "unconnected-(IC2A-NC-Pad40)") (class "Default")
      (node (ref "IC2") (pin "40") (pinfunction "NC_40") (pintype "passive"))
    )
    (net (code "161") (name "unconnected-(J4-Pad3)") (class "Default")
      (node (ref "J4") (pin "3") (pinfunction "3_3") (pintype "passive"))
    )
    (net (code "162") (name "unconnected-(R4A-Pad1)") (class "Default")
      (node (ref "R4A") (pin "1") (pinfunction "1_1") (pintype "passive"))
    )
    (net (code "163") (name "unconnected-(R5A-Pad1)") (class "Default")
      (node (ref "R5A") (pin "1") (pinfunction "1_1") (pintype "passive"))
    )
    (net (code "164") (name "unconnected-(R35-Pad1)") (class "Default")
      (node (ref "R35") (pin "1") (pinfunction "1_1") (pintype "passive"))
    )
    (net (code "165") (name "unconnected-(R36-Pad1)") (class "Default")
      (node (ref "R36") (pin "1") (pinfunction "1_1") (pintype "passive"))
    )
    (net (code "166") (name "unconnected-(U$1-INTRP-PadP$32)") (class "Default")
      (node (ref "U$1") (pin "P$32") (pinfunction "INTRP_P$32") (pintype "passive"))
    )
    (net (code "167") (name "unconnected-(U$1-MDC-PadP$19)") (class "Default")
      (node (ref "U$1") (pin "P$19") (pinfunction "MDC_P$19") (pintype "passive"))
    )
    (net (code "168") (name "unconnected-(U$1-MDIO-PadP$18)") (class "Default")
      (node (ref "U$1") (pin "P$18") (pinfunction "MDIO_P$18") (pintype "passive"))
    )
    (net (code "169") (name "unconnected-(U$1-NC_1-PadP$44)") (class "Default")
      (node (ref "U$1") (pin "P$44") (pinfunction "NC_1_P$44") (pintype "passive"))
    )
    (net (code "170") (name "unconnected-(U$1-NC_2-PadP$45)") (class "Default")
      (node (ref "U$1") (pin "P$45") (pinfunction "NC_2_P$45") (pintype "passive"))
    )
    (net (code "171") (name "unconnected-(U$1-NC_3-PadP$46)") (class "Default")
      (node (ref "U$1") (pin "P$46") (pinfunction "NC_3_P$46") (pintype "passive"))
    )
    (net (code "172") (name "unconnected-(U$1-NC_4-PadP$48)") (class "Default")
      (node (ref "U$1") (pin "P$48") (pinfunction "NC_4_P$48") (pintype "passive"))
    )
    (net (code "173") (name "unconnected-(U$1-RX--PadP$9)") (class "Default")
      (node (ref "U$1") (pin "P$9") (pinfunction "RX-_P$9") (pintype "passive"))
    )
    (net (code "174") (name "unconnected-(U$1-RXC-PadP$28)") (class "Default")
      (node (ref "U$1") (pin "P$28") (pinfunction "RXC_P$28") (pintype "passive"))
    )
    (net (code "175") (name "unconnected-(U$1-RXD2{slash}PHYAD1-PadP$21)") (class "Default")
      (node (ref "U$1") (pin "P$21") (pinfunction "RXD2/PHYAD1_P$21") (pintype "passive"))
    )
    (net (code "176") (name "unconnected-(U$1-RXD3{slash}PHYAD0-PadP$20)") (class "Default")
      (node (ref "U$1") (pin "P$20") (pinfunction "RXD3/PHYAD0_P$20") (pintype "passive"))
    )
    (net (code "177") (name "unconnected-(U$1-TXC-PadP$33)") (class "Default")
      (node (ref "U$1") (pin "P$33") (pinfunction "TXC_P$33") (pintype "passive"))
    )
    (net (code "178") (name "unconnected-(U$1-TXD2-PadP$38)") (class "Default")
      (node (ref "U$1") (pin "P$38") (pinfunction "TXD2_P$38") (pintype "passive"))
    )
    (net (code "179") (name "unconnected-(U$1-TXD3-PadP$39)") (class "Default")
      (node (ref "U$1") (pin "P$39") (pinfunction "TXD3_P$39") (pintype "passive"))
    )
    (net (code "180") (name "unconnected-(U$1-XO-PadP$14)") (class "Default")
      (node (ref "U$1") (pin "P$14") (pinfunction "XO_P$14") (pintype "passive"))
    )
    (net (code "181") (name "unconnected-(U$2-PadGND)") (class "Default")
      (node (ref "U$2") (pin "GND") (pinfunction "GND_GND") (pintype "passive"))
    )
    (net (code "182") (name "unconnected-(U3-A10-Pad87)") (class "Default")
      (node (ref "U3") (pin "87") (pinfunction "A10_87") (pintype "passive"))
    )
    (net (code "183") (name "unconnected-(U3-A14-Pad83)") (class "Default")
      (node (ref "U3") (pin "83") (pinfunction "A14_83") (pintype "passive"))
    )
    (net (code "184") (name "unconnected-(U3-A15-Pad82)") (class "Default")
      (node (ref "U3") (pin "82") (pinfunction "A15_82") (pintype "passive"))
    )
    (net (code "185") (name "unconnected-(U3-A18-Pad79)") (class "Default")
      (node (ref "U3") (pin "79") (pinfunction "A18_79") (pintype "passive"))
    )
    (net (code "186") (name "unconnected-(U3-A19-Pad76)") (class "Default")
      (node (ref "U3") (pin "76") (pinfunction "A19_76") (pintype "passive"))
    )
    (net (code "187") (name "unconnected-(U3-A20-Pad75)") (class "Default")
      (node (ref "U3") (pin "75") (pinfunction "A20_75") (pintype "passive"))
    )
    (net (code "188") (name "unconnected-(U3-A21-Pad74)") (class "Default")
      (node (ref "U3") (pin "74") (pinfunction "A21_74") (pintype "passive"))
    )
    (net (code "189") (name "unconnected-(U3-A22-Pad73)") (class "Default")
      (node (ref "U3") (pin "73") (pinfunction "A22_73") (pintype "passive"))
    )
    (net (code "190") (name "unconnected-(U3-CFCE1{slash}TIOB2{slash}PC6-Pad63)") (class "Default")
      (node (ref "U3") (pin "63") (pinfunction "CFCE1/TIOB2/PC6_63") (pintype "passive"))
    )
    (net (code "191") (name "unconnected-(U3-CFCE2{slash}TIOB1{slash}PC7-Pad64)") (class "Default")
      (node (ref "U3") (pin "64") (pinfunction "CFCE2/TIOB1/PC7_64") (pintype "passive"))
    )
    (net (code "192") (name "unconnected-(U3-CFIOW{slash}NBS3{slash}NWR3-Pad101)") (class "Default")
      (node (ref "U3") (pin "101") (pinfunction "CFIOW/NBS3/NWR3_101") (pintype "passive"))
    )
    (net (code "193") (name "unconnected-(U3-CFOE{slash}NRD-Pad69)") (class "Default")
      (node (ref "U3") (pin "69") (pinfunction "CFOE/NRD_69") (pintype "passive"))
    )
    (net (code "194") (name "unconnected-(U3-CFWE{slash}NWE{slash}NWR0-Pad70)") (class "Default")
      (node (ref "U3") (pin "70") (pinfunction "CFWE/NWE/NWR0_70") (pintype "passive"))
    )
    (net (code "195") (name "unconnected-(U3-CTS3{slash}A25_CFRNW{slash}PC10-Pad58)") (class "Default")
      (node (ref "U3") (pin "58") (pinfunction "CTS3/A25_CFRNW/PC10_58") (pintype "passive"))
    )
    (net (code "196") (name "unconnected-(U3-D0-Pad106)") (class "Default")
      (node (ref "U3") (pin "106") (pinfunction "D0_106") (pintype "passive"))
    )
    (net (code "197") (name "unconnected-(U3-D1-Pad107)") (class "Default")
      (node (ref "U3") (pin "107") (pinfunction "D1_107") (pintype "passive"))
    )
    (net (code "198") (name "unconnected-(U3-D2-Pad108)") (class "Default")
      (node (ref "U3") (pin "108") (pinfunction "D2_108") (pintype "passive"))
    )
    (net (code "199") (name "unconnected-(U3-D3-Pad109)") (class "Default")
      (node (ref "U3") (pin "109") (pinfunction "D3_109") (pintype "passive"))
    )
    (net (code "200") (name "unconnected-(U3-D4-Pad110)") (class "Default")
      (node (ref "U3") (pin "110") (pinfunction "D4_110") (pintype "passive"))
    )
    (net (code "201") (name "unconnected-(U3-D5-Pad111)") (class "Default")
      (node (ref "U3") (pin "111") (pinfunction "D5_111") (pintype "passive"))
    )
    (net (code "202") (name "unconnected-(U3-D6-Pad112)") (class "Default")
      (node (ref "U3") (pin "112") (pinfunction "D6_112") (pintype "passive"))
    )
    (net (code "203") (name "unconnected-(U3-D7-Pad118)") (class "Default")
      (node (ref "U3") (pin "118") (pinfunction "D7_118") (pintype "passive"))
    )
    (net (code "204") (name "unconnected-(U3-D8-Pad119)") (class "Default")
      (node (ref "U3") (pin "119") (pinfunction "D8_119") (pintype "passive"))
    )
    (net (code "205") (name "unconnected-(U3-D9-Pad120)") (class "Default")
      (node (ref "U3") (pin "120") (pinfunction "D9_120") (pintype "passive"))
    )
    (net (code "206") (name "unconnected-(U3-D10-Pad121)") (class "Default")
      (node (ref "U3") (pin "121") (pinfunction "D10_121") (pintype "passive"))
    )
    (net (code "207") (name "unconnected-(U3-D11-Pad122)") (class "Default")
      (node (ref "U3") (pin "122") (pinfunction "D11_122") (pintype "passive"))
    )
    (net (code "208") (name "unconnected-(U3-D12-Pad123)") (class "Default")
      (node (ref "U3") (pin "123") (pinfunction "D12_123") (pintype "passive"))
    )
    (net (code "209") (name "unconnected-(U3-D13-Pad124)") (class "Default")
      (node (ref "U3") (pin "124") (pinfunction "D13_124") (pintype "passive"))
    )
    (net (code "210") (name "unconnected-(U3-D23{slash}PC23-Pad137)") (class "Default")
      (node (ref "U3") (pin "137") (pinfunction "D23/PC23_137") (pintype "passive"))
    )
    (net (code "211") (name "unconnected-(U3-D24{slash}PC24-Pad138)") (class "Default")
      (node (ref "U3") (pin "138") (pinfunction "D24/PC24_138") (pintype "passive"))
    )
    (net (code "212") (name "unconnected-(U3-D25{slash}PC25-Pad139)") (class "Default")
      (node (ref "U3") (pin "139") (pinfunction "D25/PC25_139") (pintype "passive"))
    )
    (net (code "213") (name "unconnected-(U3-D26{slash}PC26-Pad140)") (class "Default")
      (node (ref "U3") (pin "140") (pinfunction "D26/PC26_140") (pintype "passive"))
    )
    (net (code "214") (name "unconnected-(U3-D27{slash}PC27-Pad141)") (class "Default")
      (node (ref "U3") (pin "141") (pinfunction "D27/PC27_141") (pintype "passive"))
    )
    (net (code "215") (name "unconnected-(U3-D28{slash}PC28-Pad142)") (class "Default")
      (node (ref "U3") (pin "142") (pinfunction "D28/PC28_142") (pintype "passive"))
    )
    (net (code "216") (name "unconnected-(U3-EF100{slash}D21{slash}PC21-Pad135)") (class "Default")
      (node (ref "U3") (pin "135") (pinfunction "EF100/D21/PC21_135") (pintype "passive"))
    )
    (net (code "217") (name "unconnected-(U3-ISI_D0{slash}RK0{slash}PB20-Pad163)") (class "Default")
      (node (ref "U3") (pin "163") (pinfunction "ISI_D0/RK0/PB20_163") (pintype "passive"))
    )
    (net (code "218") (name "unconnected-(U3-ISI_D1{slash}RF0{slash}PB21-Pad164)") (class "Default")
      (node (ref "U3") (pin "164") (pinfunction "ISI_D1/RF0/PB21_164") (pintype "passive"))
    )
    (net (code "219") (name "unconnected-(U3-ISI_D2{slash}DSR0{slash}PB22-Pad165)") (class "Default")
      (node (ref "U3") (pin "165") (pinfunction "ISI_D2/DSR0/PB22_165") (pintype "passive"))
    )
    (net (code "220") (name "unconnected-(U3-ISI_D3{slash}DCD0{slash}PB23-Pad166)") (class "Default")
      (node (ref "U3") (pin "166") (pinfunction "ISI_D3/DCD0/PB23_166") (pintype "passive"))
    )
    (net (code "221") (name "unconnected-(U3-ISI_D4{slash}DTR0{slash}PB24-Pad167)") (class "Default")
      (node (ref "U3") (pin "167") (pinfunction "ISI_D4/DTR0/PB24_167") (pintype "passive"))
    )
    (net (code "222") (name "unconnected-(U3-ISI_D5{slash}RI0{slash}PB25-Pad168)") (class "Default")
      (node (ref "U3") (pin "168") (pinfunction "ISI_D5/RI0/PB25_168") (pintype "passive"))
    )
    (net (code "223") (name "unconnected-(U3-ISI_D6{slash}RTS0{slash}PB26-Pad171)") (class "Default")
      (node (ref "U3") (pin "171") (pinfunction "ISI_D6/RTS0/PB26_171") (pintype "passive"))
    )
    (net (code "224") (name "unconnected-(U3-ISI_D7{slash}CTS0{slash}PB27-Pad172)") (class "Default")
      (node (ref "U3") (pin "172") (pinfunction "ISI_D7/CTS0/PB27_172") (pintype "passive"))
    )
    (net (code "225") (name "unconnected-(U3-ISI_D8{slash}TXD3{slash}PB10-Pad161)") (class "Default")
      (node (ref "U3") (pin "161") (pinfunction "ISI_D8/TXD3/PB10_161") (pintype "passive"))
    )
    (net (code "226") (name "unconnected-(U3-ISI_D9{slash}RXD3{slash}PB11-Pad162)") (class "Default")
      (node (ref "U3") (pin "162") (pinfunction "ISI_D9/RXD3/PB11_162") (pintype "passive"))
    )
    (net (code "227") (name "unconnected-(U3-ISI_HSYNC{slash}PCK0{slash}PB30-Pad177)") (class "Default")
      (node (ref "U3") (pin "177") (pinfunction "ISI_HSYNC/PCK0/PB30_177") (pintype "passive"))
    )
    (net (code "228") (name "unconnected-(U3-ISI_MCK{slash}PCK1{slash}PB31-Pad178)") (class "Default")
      (node (ref "U3") (pin "178") (pinfunction "ISI_MCK/PCK1/PB31_178") (pintype "passive"))
    )
    (net (code "229") (name "unconnected-(U3-ISI_PCK{slash}RTS1{slash}PB28-Pad175)") (class "Default")
      (node (ref "U3") (pin "175") (pinfunction "ISI_PCK/RTS1/PB28_175") (pintype "passive"))
    )
    (net (code "230") (name "unconnected-(U3-ISI_VSYNC{slash}CTS1{slash}PB29-Pad176)") (class "Default")
      (node (ref "U3") (pin "176") (pinfunction "ISI_VSYNC/CTS1/PB29_176") (pintype "passive"))
    )
    (net (code "231") (name "unconnected-(U3-NANDOE-Pad71)") (class "Default")
      (node (ref "U3") (pin "71") (pinfunction "NANDOE_71") (pintype "passive"))
    )
    (net (code "232") (name "unconnected-(U3-NANDWE-Pad72)") (class "Default")
      (node (ref "U3") (pin "72") (pinfunction "NANDWE_72") (pintype "passive"))
    )
    (net (code "233") (name "unconnected-(U3-NC@152-Pad152)") (class "Default")
      (node (ref "U3") (pin "152") (pinfunction "NC@152_152") (pintype "passive"))
    )
    (net (code "234") (name "unconnected-(U3-NCS6{slash}FIQ{slash}PC13-Pad56)") (class "Default")
      (node (ref "U3") (pin "56") (pinfunction "NCS6/FIQ/PC13_56") (pintype "passive"))
    )
    (net (code "235") (name "unconnected-(U3-NCSO-Pad68)") (class "Default")
      (node (ref "U3") (pin "68") (pinfunction "NCSO_68") (pintype "passive"))
    )
    (net (code "236") (name "unconnected-(U3-PA4{slash}RTS2{slash}MCDB2-Pad183)") (class "Default")
      (node (ref "U3") (pin "183") (pinfunction "PA4/RTS2/MCDB2_183") (pintype "passive"))
    )
    (net (code "237") (name "unconnected-(U3-PA5{slash}CTS2{slash}MCDB1-Pad184)") (class "Default")
      (node (ref "U3") (pin "184") (pinfunction "PA5/CTS2/MCDB1_184") (pintype "passive"))
    )
    (net (code "238") (name "unconnected-(U3-PA20{slash}EMDC-Pad205)") (class "Default")
      (node (ref "U3") (pin "205") (pinfunction "PA20/EMDC_205") (pintype "passive"))
    )
    (net (code "239") (name "unconnected-(U3-PA21{slash}EMDIO-Pad206)") (class "Default")
      (node (ref "U3") (pin "206") (pinfunction "PA21/EMDIO_206") (pintype "passive"))
    )
    (net (code "240") (name "unconnected-(U3-PA22{slash}ADTRG{slash}ETXER-Pad207)") (class "Default")
      (node (ref "U3") (pin "207") (pinfunction "PA22/ADTRG/ETXER_207") (pintype "passive"))
    )
    (net (code "241") (name "unconnected-(U3-PA25{slash}TLCK0{slash}ERX2-Pad2)") (class "Default")
      (node (ref "U3") (pin "2") (pinfunction "PA25/TLCK0/ERX2_2") (pintype "passive"))
    )
    (net (code "242") (name "unconnected-(U3-PA27{slash}TIOA1{slash}ERXCK-Pad4)") (class "Default")
      (node (ref "U3") (pin "4") (pinfunction "PA27/TIOA1/ERXCK_4") (pintype "passive"))
    )
    (net (code "243") (name "unconnected-(U3-PA28{slash}TIOA2{slash}ECRS-Pad7)") (class "Default")
      (node (ref "U3") (pin "7") (pinfunction "PA28/TIOA2/ECRS_7") (pintype "passive"))
    )
    (net (code "244") (name "unconnected-(U3-PA29{slash}SCK1{slash}ECOL-Pad8)") (class "Default")
      (node (ref "U3") (pin "8") (pinfunction "PA29/SCK1/ECOL_8") (pintype "passive"))
    )
    (net (code "245") (name "unconnected-(U3-RTS3{slash}NCS4_CFCS0{slash}PC8-Pad61)") (class "Default")
      (node (ref "U3") (pin "61") (pinfunction "RTS3/NCS4_CFCS0/PC8_61") (pintype "passive"))
    )
    (net (code "246") (name "unconnected-(U3-SPI0_NPCS1{slash}NCS2{slash}PC11-Pad57)") (class "Default")
      (node (ref "U3") (pin "57") (pinfunction "SPI0_NPCS1/NCS2/PC11_57") (pintype "passive"))
    )
    (net (code "247") (name "unconnected-(U3-SPI0_NPCS2{slash}D16{slash}PC16-Pad128)") (class "Default")
      (node (ref "U3") (pin "128") (pinfunction "SPI0_NPCS2/D16/PC16_128") (pintype "passive"))
    )
    (net (code "248") (name "unconnected-(U3-SPI0_NPCS3{slash}D17{slash}PC17-Pad129)") (class "Default")
      (node (ref "U3") (pin "129") (pinfunction "SPI0_NPCS3/D17/PC17_129") (pintype "passive"))
    )
    (net (code "249") (name "unconnected-(U3-SPI1_NPCS1{slash}D18{slash}PC18-Pad130)") (class "Default")
      (node (ref "U3") (pin "130") (pinfunction "SPI1_NPCS1/D18/PC18_130") (pintype "passive"))
    )
    (net (code "250") (name "unconnected-(U3-SPI1_NPCS2{slash}D19{slash}PC19-Pad131)") (class "Default")
      (node (ref "U3") (pin "131") (pinfunction "SPI1_NPCS2/D19/PC19_131") (pintype "passive"))
    )
    (net (code "251") (name "unconnected-(U3-SPI1_NPCS3{slash}D20{slash}PC20-Pad134)") (class "Default")
      (node (ref "U3") (pin "134") (pinfunction "SPI1_NPCS3/D20/PC20_134") (pintype "passive"))
    )
    (net (code "252") (name "unconnected-(U3-TCLK5{slash}D22{slash}PC22-Pad136)") (class "Default")
      (node (ref "U3") (pin "136") (pinfunction "TCLK5/D22/PC22_136") (pintype "passive"))
    )
    (net (code "253") (name "unconnected-(U3-TIOB0{slash}NCS5_CFCS1{slash}PC9-Pad60)") (class "Default")
      (node (ref "U3") (pin "60") (pinfunction "TIOB0/NCS5_CFCS1/PC9_60") (pintype "passive"))
    )
    (net (code "254") (name "unconnected-(VR1-BYP-Pad4)") (class "Default")
      (node (ref "VR1") (pin "4") (pinfunction "BYP_4") (pintype "passive"))
    )
  )
)
